# TC_board.net
KiCad netlist of a schematic drawn in EAGLE
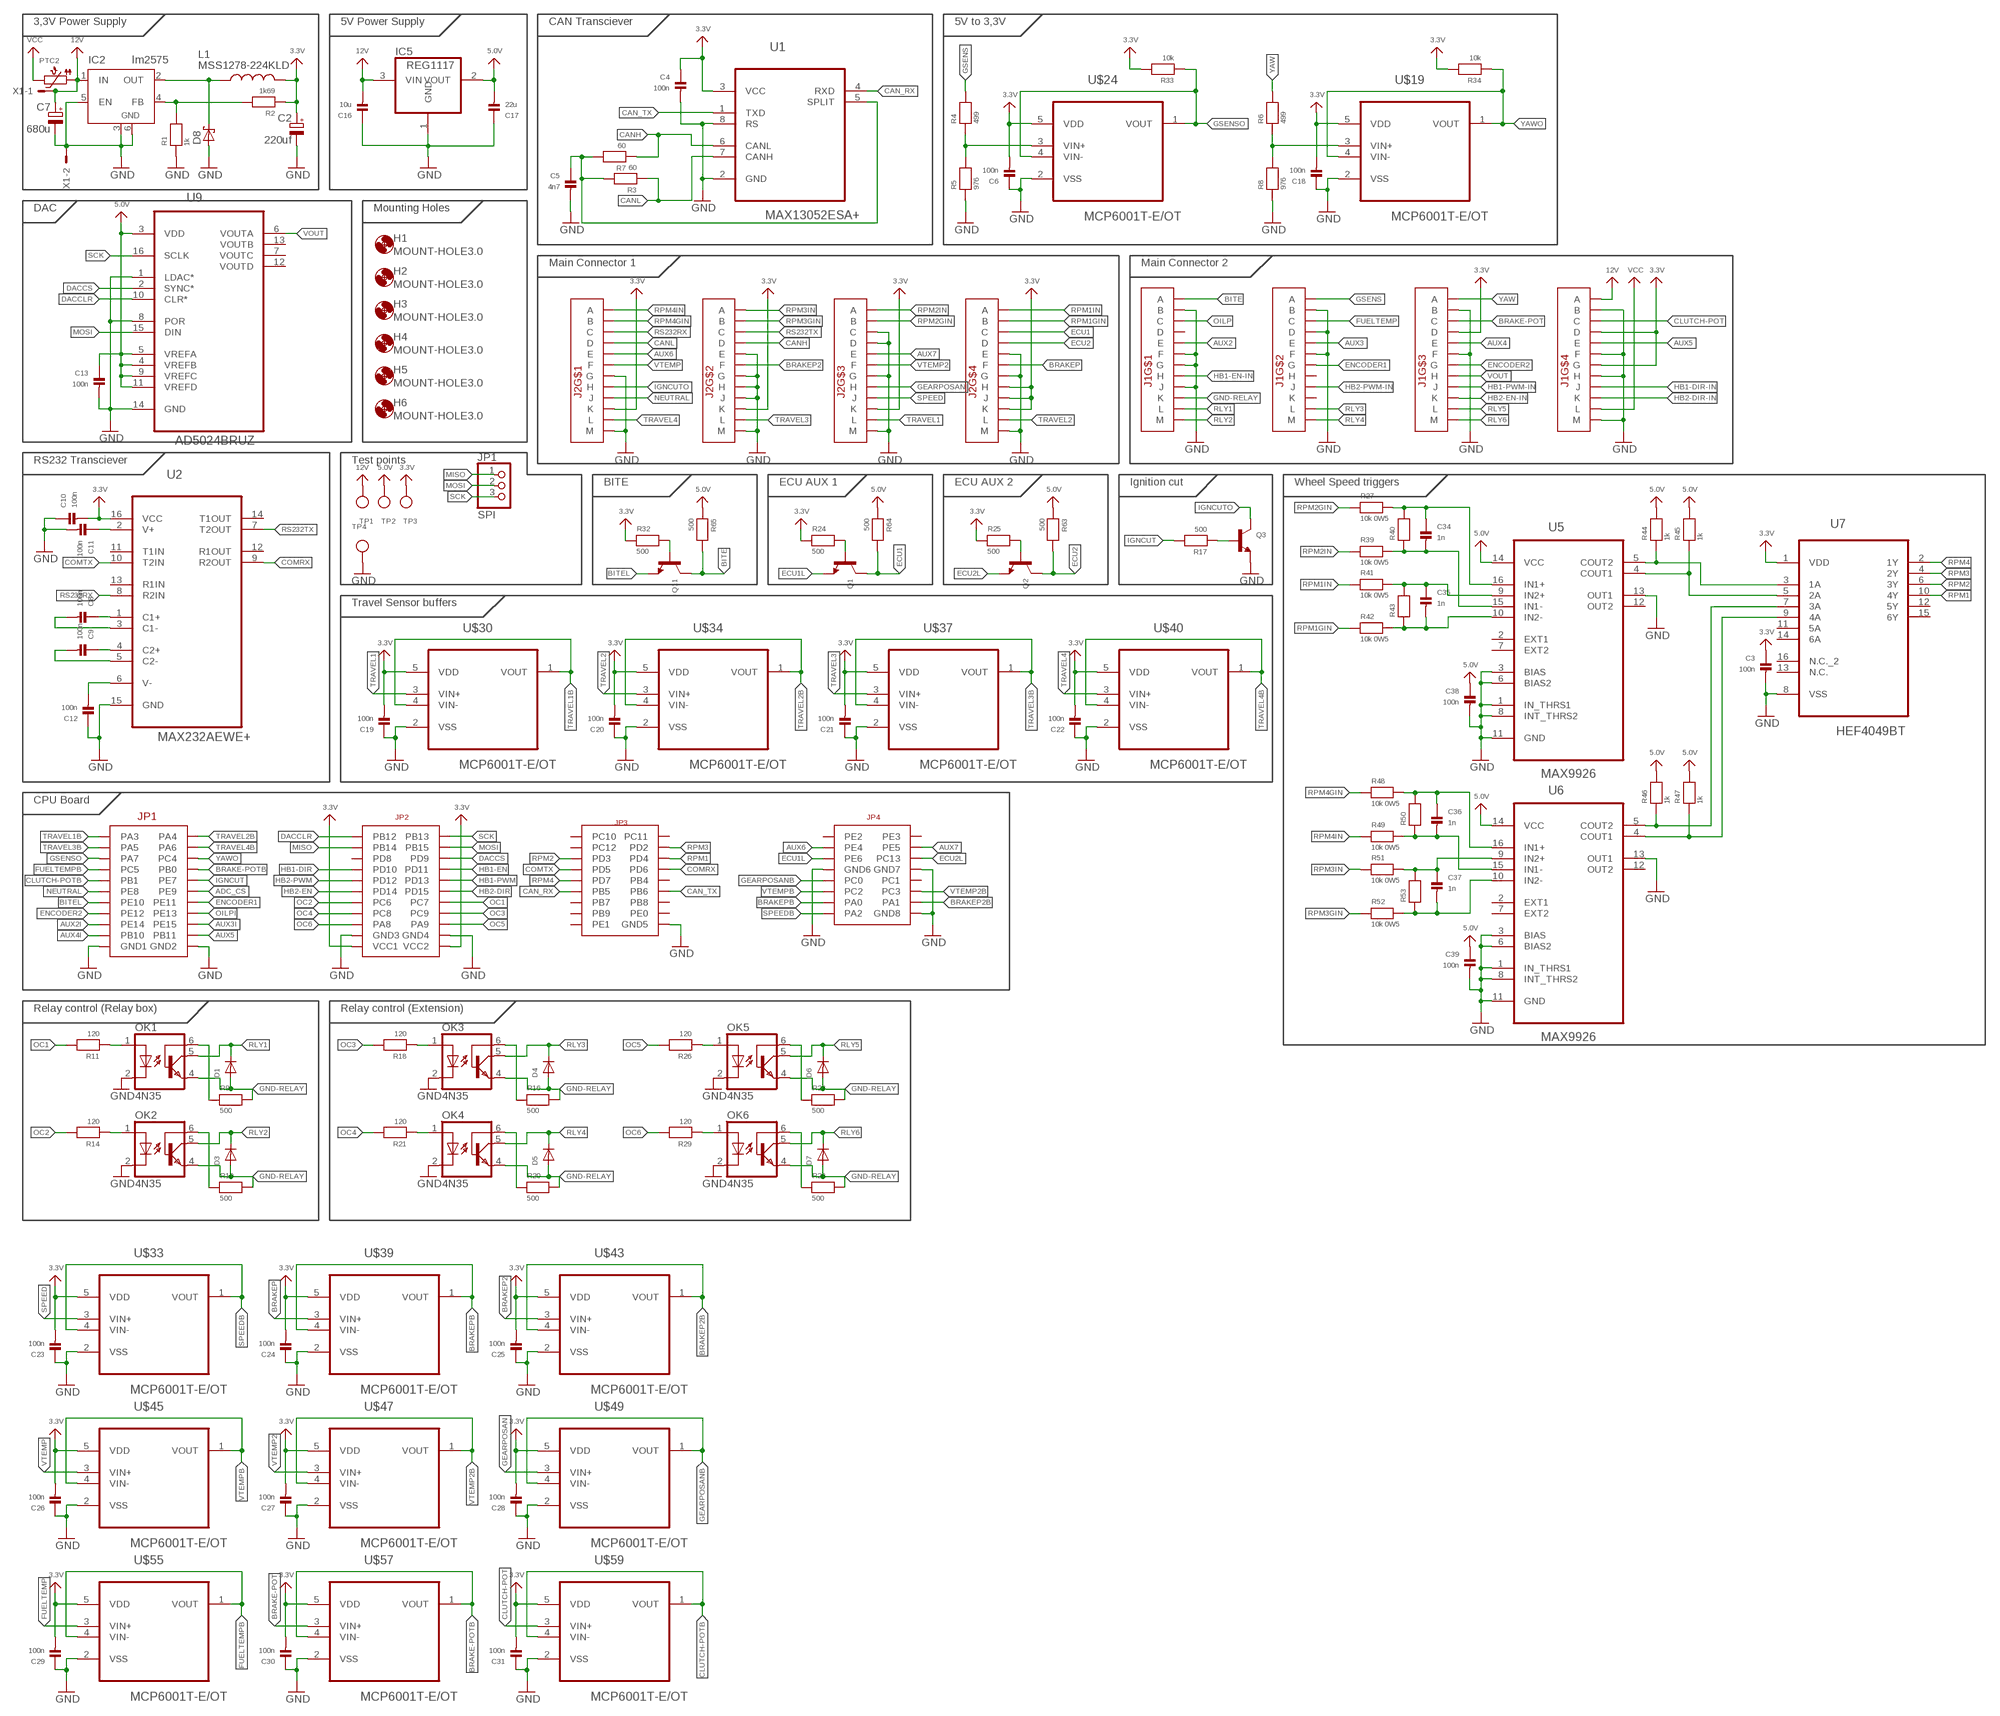
[diagram p0: schematic, sheet 1, part 1 of 2]
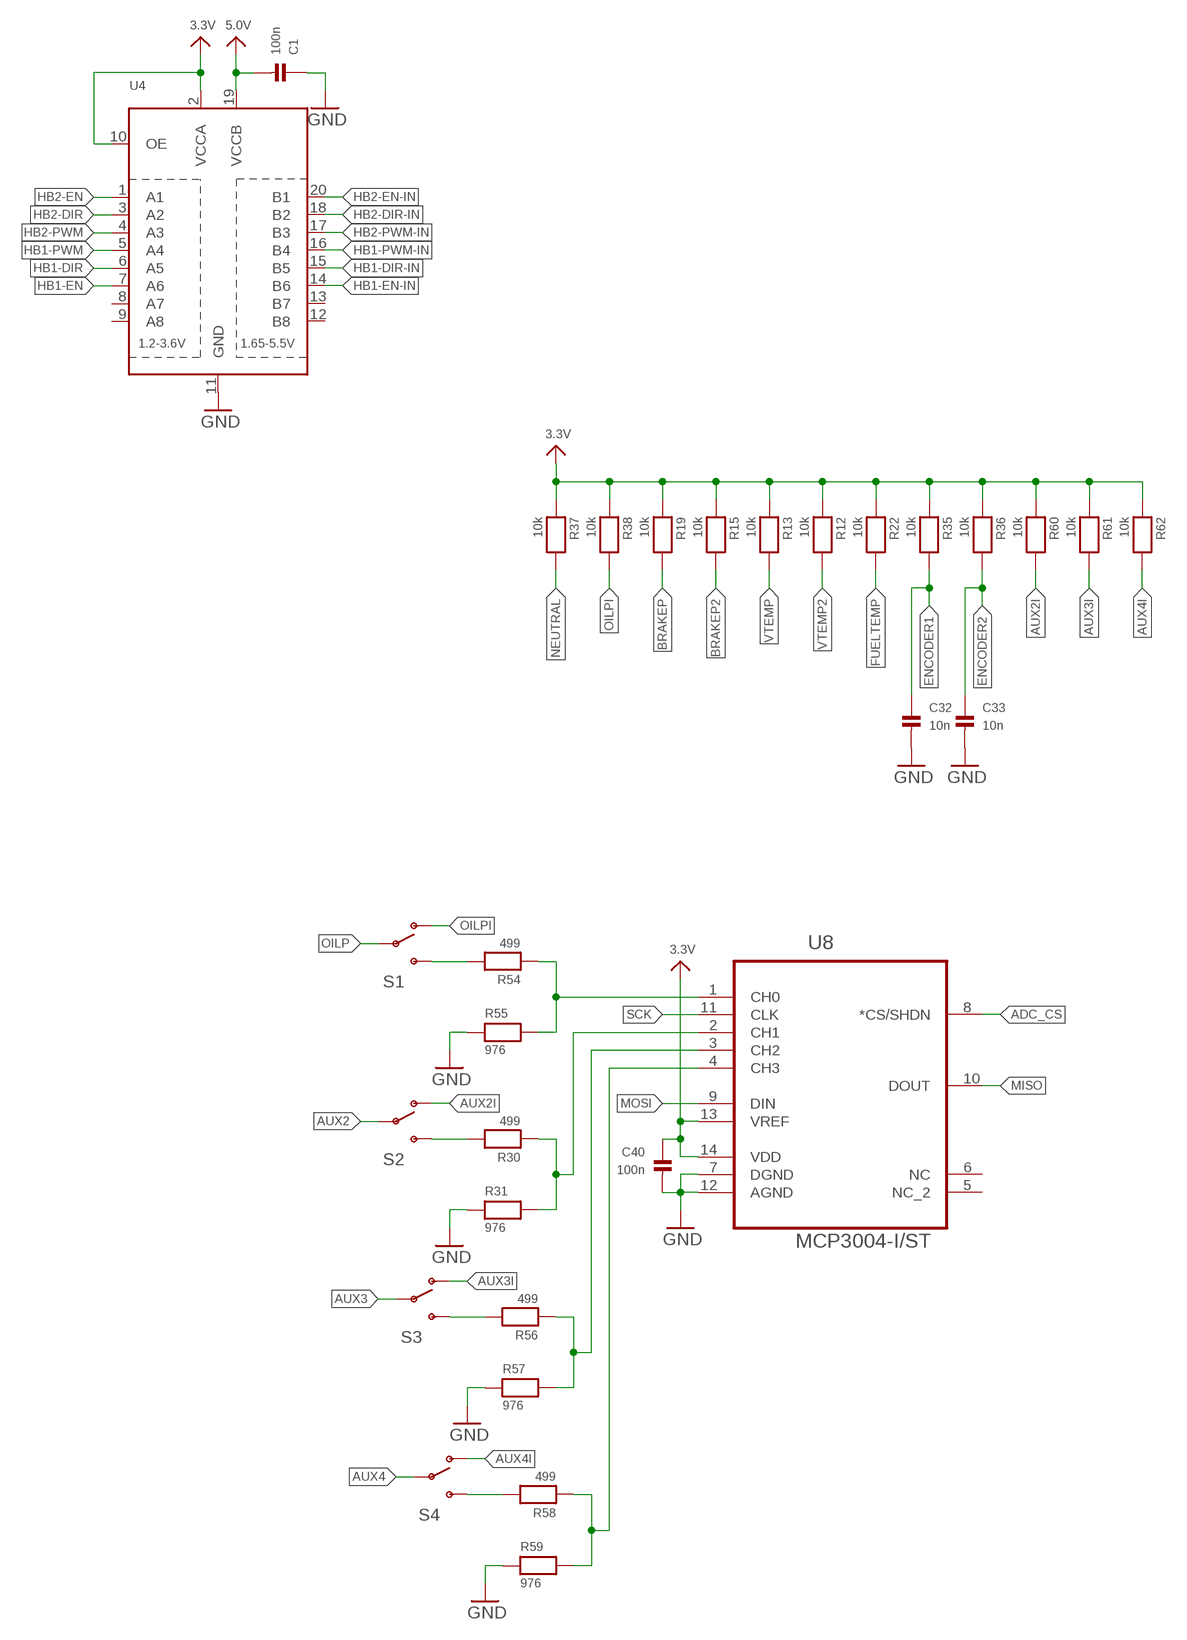
[diagram p1: schematic, sheet 1, part 2 of 2]

(export (version "E")
  (design (tool "Eeschema 10.0.6"))
  (components
    (comp (ref "C1")
      (value "100n")
      (footprint "eagle-import:_0603")
      (libsource (lib "eagle-import") (part "CAP_CERAMIC_0603"))
    )
    (comp (ref "C2")
      (value "220uf")
      (footprint "eagle-import:E3,5-8")
      (libsource (lib "eagle-import") (part "CPOL-EUE3.5-8"))
    )
    (comp (ref "C3")
      (value "100n")
      (footprint "eagle-import:_0603")
      (libsource (lib "eagle-import") (part "CAP_CERAMIC_0603"))
    )
    (comp (ref "C4")
      (value "100n")
      (footprint "eagle-import:_0603")
      (libsource (lib "eagle-import") (part "CAP_CERAMIC_0603"))
    )
    (comp (ref "C5")
      (value "4n7")
      (footprint "eagle-import:_0603")
      (libsource (lib "eagle-import") (part "CAP_CERAMIC_0603"))
    )
    (comp (ref "C6")
      (value "100n")
      (footprint "eagle-import:_0603")
      (libsource (lib "eagle-import") (part "CAP_CERAMIC_0603"))
    )
    (comp (ref "C7")
      (value "680u")
      (footprint "eagle-import:E5-10,5")
      (libsource (lib "eagle-import") (part "CPOL-EUE5-10.5"))
    )
    (comp (ref "C8")
      (value "100n")
      (footprint "eagle-import:_0603")
      (libsource (lib "eagle-import") (part "CAP_CERAMIC_0603"))
    )
    (comp (ref "C9")
      (value "100n")
      (footprint "eagle-import:_0603")
      (libsource (lib "eagle-import") (part "CAP_CERAMIC_0603"))
    )
    (comp (ref "C10")
      (value "100n")
      (footprint "eagle-import:_0603")
      (libsource (lib "eagle-import") (part "CAP_CERAMIC_0603"))
    )
    (comp (ref "C11")
      (value "100n")
      (footprint "eagle-import:_0603")
      (libsource (lib "eagle-import") (part "CAP_CERAMIC_0603"))
    )
    (comp (ref "C12")
      (value "100n")
      (footprint "eagle-import:_0603")
      (libsource (lib "eagle-import") (part "CAP_CERAMIC_0603"))
    )
    (comp (ref "C13")
      (value "100n")
      (footprint "eagle-import:_0603")
      (libsource (lib "eagle-import") (part "CAP_CERAMIC_0603"))
    )
    (comp (ref "C16")
      (value "10u")
      (footprint "eagle-import:_0805")
      (libsource (lib "eagle-import") (part "CAP_CERAMIC_0805"))
    )
    (comp (ref "C17")
      (value "22u")
      (footprint "eagle-import:_0805")
      (libsource (lib "eagle-import") (part "CAP_CERAMIC_0805"))
    )
    (comp (ref "C18")
      (value "100n")
      (footprint "eagle-import:_0603")
      (libsource (lib "eagle-import") (part "CAP_CERAMIC_0603"))
    )
    (comp (ref "C19")
      (value "100n")
      (footprint "eagle-import:_0603")
      (libsource (lib "eagle-import") (part "CAP_CERAMIC_0603"))
    )
    (comp (ref "C20")
      (value "100n")
      (footprint "eagle-import:_0603")
      (libsource (lib "eagle-import") (part "CAP_CERAMIC_0603"))
    )
    (comp (ref "C21")
      (value "100n")
      (footprint "eagle-import:_0603")
      (libsource (lib "eagle-import") (part "CAP_CERAMIC_0603"))
    )
    (comp (ref "C22")
      (value "100n")
      (footprint "eagle-import:_0603")
      (libsource (lib "eagle-import") (part "CAP_CERAMIC_0603"))
    )
    (comp (ref "C23")
      (value "100n")
      (footprint "eagle-import:_0603")
      (libsource (lib "eagle-import") (part "CAP_CERAMIC_0603"))
    )
    (comp (ref "C24")
      (value "100n")
      (footprint "eagle-import:_0603")
      (libsource (lib "eagle-import") (part "CAP_CERAMIC_0603"))
    )
    (comp (ref "C25")
      (value "100n")
      (footprint "eagle-import:_0603")
      (libsource (lib "eagle-import") (part "CAP_CERAMIC_0603"))
    )
    (comp (ref "C26")
      (value "100n")
      (footprint "eagle-import:_0603")
      (libsource (lib "eagle-import") (part "CAP_CERAMIC_0603"))
    )
    (comp (ref "C27")
      (value "100n")
      (footprint "eagle-import:_0603")
      (libsource (lib "eagle-import") (part "CAP_CERAMIC_0603"))
    )
    (comp (ref "C28")
      (value "100n")
      (footprint "eagle-import:_0603")
      (libsource (lib "eagle-import") (part "CAP_CERAMIC_0603"))
    )
    (comp (ref "C29")
      (value "100n")
      (footprint "eagle-import:_0603")
      (libsource (lib "eagle-import") (part "CAP_CERAMIC_0603"))
    )
    (comp (ref "C30")
      (value "100n")
      (footprint "eagle-import:_0603")
      (libsource (lib "eagle-import") (part "CAP_CERAMIC_0603"))
    )
    (comp (ref "C31")
      (value "100n")
      (footprint "eagle-import:_0603")
      (libsource (lib "eagle-import") (part "CAP_CERAMIC_0603"))
    )
    (comp (ref "C32")
      (value "10n")
      (footprint "eagle-import:_0603")
      (libsource (lib "eagle-import") (part "CAP_CERAMIC_0603"))
    )
    (comp (ref "C33")
      (value "10n")
      (footprint "eagle-import:_0603")
      (libsource (lib "eagle-import") (part "CAP_CERAMIC_0603"))
    )
    (comp (ref "C34")
      (value "1n")
      (footprint "eagle-import:_0603")
      (libsource (lib "eagle-import") (part "CAP_CERAMIC_0603"))
    )
    (comp (ref "C35")
      (value "1n")
      (footprint "eagle-import:_0603")
      (libsource (lib "eagle-import") (part "CAP_CERAMIC_0603"))
    )
    (comp (ref "C36")
      (value "1n")
      (footprint "eagle-import:_0603")
      (libsource (lib "eagle-import") (part "CAP_CERAMIC_0603"))
    )
    (comp (ref "C37")
      (value "1n")
      (footprint "eagle-import:_0603")
      (libsource (lib "eagle-import") (part "CAP_CERAMIC_0603"))
    )
    (comp (ref "C38")
      (value "100n")
      (footprint "eagle-import:_0603")
      (libsource (lib "eagle-import") (part "CAP_CERAMIC_0603"))
    )
    (comp (ref "C39")
      (value "100n")
      (footprint "eagle-import:_0603")
      (libsource (lib "eagle-import") (part "CAP_CERAMIC_0603"))
    )
    (comp (ref "C40")
      (value "100n")
      (footprint "eagle-import:_0603")
      (libsource (lib "eagle-import") (part "CAP_CERAMIC_0603"))
    )
    (comp (ref "D1")
      (value "DIODESOD-323F")
      (footprint "eagle-import:SOD-323F")
      (libsource (lib "eagle-import") (part "DIODESOD-323F"))
    )
    (comp (ref "D3")
      (value "DIODESOD-323F")
      (footprint "eagle-import:SOD-323F")
      (libsource (lib "eagle-import") (part "DIODESOD-323F"))
    )
    (comp (ref "D4")
      (value "DIODESOD-323F")
      (footprint "eagle-import:SOD-323F")
      (libsource (lib "eagle-import") (part "DIODESOD-323F"))
    )
    (comp (ref "D5")
      (value "DIODESOD-323F")
      (footprint "eagle-import:SOD-323F")
      (libsource (lib "eagle-import") (part "DIODESOD-323F"))
    )
    (comp (ref "D6")
      (value "DIODESOD-323F")
      (footprint "eagle-import:SOD-323F")
      (libsource (lib "eagle-import") (part "DIODESOD-323F"))
    )
    (comp (ref "D7")
      (value "DIODESOD-323F")
      (footprint "eagle-import:SOD-323F")
      (libsource (lib "eagle-import") (part "DIODESOD-323F"))
    )
    (comp (ref "D8")
      (value "SCHOTTKY-DIODESMC")
      (footprint "eagle-import:SMC")
      (libsource (lib "eagle-import") (part "SCHOTTKY-DIODESMC"))
    )
    (comp (ref "H1")
      (value "MOUNT-HOLE3.0")
      (footprint "eagle-import:3,0")
      (libsource (lib "eagle-import") (part "MOUNT-HOLE3.0"))
    )
    (comp (ref "H2")
      (value "MOUNT-HOLE3.0")
      (footprint "eagle-import:3,0")
      (libsource (lib "eagle-import") (part "MOUNT-HOLE3.0"))
    )
    (comp (ref "H3")
      (value "MOUNT-HOLE3.0")
      (footprint "eagle-import:3,0")
      (libsource (lib "eagle-import") (part "MOUNT-HOLE3.0"))
    )
    (comp (ref "H4")
      (value "MOUNT-HOLE3.0")
      (footprint "eagle-import:3,0")
      (libsource (lib "eagle-import") (part "MOUNT-HOLE3.0"))
    )
    (comp (ref "H5")
      (value "MOUNT-HOLE3.0")
      (footprint "eagle-import:3,0")
      (libsource (lib "eagle-import") (part "MOUNT-HOLE3.0"))
    )
    (comp (ref "H6")
      (value "MOUNT-HOLE3.0")
      (footprint "eagle-import:3,0")
      (libsource (lib "eagle-import") (part "MOUNT-HOLE3.0"))
    )
    (comp (ref "IC2")
      (value "lm2575")
      (footprint "eagle-import:TO263-5")
      (libsource (lib "eagle-import") (part "LM2596S"))
    )
    (comp (ref "IC5")
      (value "REG1117")
      (footprint "eagle-import:SOT223")
      (libsource (lib "eagle-import") (part "REG1117"))
    )
    (comp (ref "J1")
      (value "CON1")
      (footprint "eagle-import:AUTOCONNECTOR")
      (libsource (lib "eagle-import") (part "AUTOCONNECTOR"))
    )
    (comp (ref "J2")
      (value "CON1")
      (footprint "eagle-import:AUTOCONNECTOR")
      (libsource (lib "eagle-import") (part "AUTOCONNECTOR"))
    )
    (comp (ref "JP1")
      (value "SPI")
      (footprint "eagle-import:1X03")
      (libsource (lib "eagle-import") (part "PINHD-1X3"))
    )
    (comp (ref "L1")
      (value "MSS1278-224KLD")
      (footprint "eagle-import:CDRH125")
      (libsource (lib "eagle-import") (part "INDUCTORPWR"))
    )
    (comp (ref "OK1")
      (value "4N35")
      (footprint "eagle-import:DIL06")
      (fields (field (name "MF") "FAIRCHILD SEMICONDUCTOR"))
      (libsource (lib "eagle-import") (part "4N35"))
    )
    (comp (ref "OK2")
      (value "4N35")
      (footprint "eagle-import:DIL06")
      (fields (field (name "MF") "FAIRCHILD SEMICONDUCTOR"))
      (libsource (lib "eagle-import") (part "4N35"))
    )
    (comp (ref "OK3")
      (value "4N35")
      (footprint "eagle-import:DIL06")
      (fields (field (name "MF") "FAIRCHILD SEMICONDUCTOR"))
      (libsource (lib "eagle-import") (part "4N35"))
    )
    (comp (ref "OK4")
      (value "4N35")
      (footprint "eagle-import:DIL06")
      (fields (field (name "MF") "FAIRCHILD SEMICONDUCTOR"))
      (libsource (lib "eagle-import") (part "4N35"))
    )
    (comp (ref "OK5")
      (value "4N35")
      (footprint "eagle-import:DIL06")
      (fields (field (name "MF") "FAIRCHILD SEMICONDUCTOR"))
      (libsource (lib "eagle-import") (part "4N35"))
    )
    (comp (ref "OK6")
      (value "4N35")
      (footprint "eagle-import:DIL06")
      (fields (field (name "MF") "FAIRCHILD SEMICONDUCTOR"))
      (libsource (lib "eagle-import") (part "4N35"))
    )
    (comp (ref "PTC2")
      (value "PTC1812")
      (footprint "eagle-import:PTC1812")
      (libsource (lib "eagle-import") (part "PTC1812"))
    )
    (comp (ref "Q1")
      (value "TRANSISTOR_NPNWIDE")
      (footprint "eagle-import:SOT23-WIDE")
      (libsource (lib "eagle-import") (part "TRANSISTOR_NPNWIDE"))
    )
    (comp (ref "Q2")
      (value "TRANSISTOR_NPNWIDE")
      (footprint "eagle-import:SOT23-WIDE")
      (libsource (lib "eagle-import") (part "TRANSISTOR_NPNWIDE"))
    )
    (comp (ref "Q3")
      (value "TRANSISTOR_NPNWIDE")
      (footprint "eagle-import:SOT23-WIDE")
      (libsource (lib "eagle-import") (part "TRANSISTOR_NPNWIDE"))
    )
    (comp (ref "Q11")
      (value "TRANSISTOR_NPNWIDE")
      (footprint "eagle-import:SOT23-WIDE")
      (libsource (lib "eagle-import") (part "TRANSISTOR_NPNWIDE"))
    )
    (comp (ref "R1")
      (value "1k")
      (footprint "eagle-import:_0603")
      (libsource (lib "eagle-import") (part "RESISTOR_0603"))
    )
    (comp (ref "R2")
      (value "1k69")
      (footprint "eagle-import:_0603")
      (libsource (lib "eagle-import") (part "RESISTOR_0603"))
    )
    (comp (ref "R3")
      (value "60")
      (footprint "eagle-import:_0603")
      (libsource (lib "eagle-import") (part "RESISTOR_0603"))
    )
    (comp (ref "R4")
      (value "499")
      (footprint "eagle-import:_0603")
      (libsource (lib "eagle-import") (part "RESISTOR_0603"))
    )
    (comp (ref "R5")
      (value "976")
      (footprint "eagle-import:_0603")
      (libsource (lib "eagle-import") (part "RESISTOR_0603"))
    )
    (comp (ref "R6")
      (value "499")
      (footprint "eagle-import:_0603")
      (libsource (lib "eagle-import") (part "RESISTOR_0603"))
    )
    (comp (ref "R7")
      (value "60")
      (footprint "eagle-import:_0603")
      (libsource (lib "eagle-import") (part "RESISTOR_0603"))
    )
    (comp (ref "R8")
      (value "976")
      (footprint "eagle-import:_0603")
      (libsource (lib "eagle-import") (part "RESISTOR_0603"))
    )
    (comp (ref "R9")
      (value "500")
      (footprint "eagle-import:_0603")
      (libsource (lib "eagle-import") (part "RESISTOR_0603"))
    )
    (comp (ref "R10")
      (value "500")
      (footprint "eagle-import:_0603")
      (libsource (lib "eagle-import") (part "RESISTOR_0603"))
    )
    (comp (ref "R11")
      (value "120")
      (footprint "eagle-import:_0603")
      (libsource (lib "eagle-import") (part "RESISTOR_0603"))
    )
    (comp (ref "R12")
      (value "10k")
      (footprint "eagle-import:_0603")
      (libsource (lib "eagle-import") (part "RESISTOR_0603"))
    )
    (comp (ref "R13")
      (value "10k")
      (footprint "eagle-import:_0603")
      (libsource (lib "eagle-import") (part "RESISTOR_0603"))
    )
    (comp (ref "R14")
      (value "120")
      (footprint "eagle-import:_0603")
      (libsource (lib "eagle-import") (part "RESISTOR_0603"))
    )
    (comp (ref "R15")
      (value "10k")
      (footprint "eagle-import:_0603")
      (libsource (lib "eagle-import") (part "RESISTOR_0603"))
    )
    (comp (ref "R16")
      (value "500")
      (footprint "eagle-import:_0603")
      (libsource (lib "eagle-import") (part "RESISTOR_0603"))
    )
    (comp (ref "R17")
      (value "500")
      (footprint "eagle-import:_0603")
      (libsource (lib "eagle-import") (part "RESISTOR_0603"))
    )
    (comp (ref "R18")
      (value "120")
      (footprint "eagle-import:_0603")
      (libsource (lib "eagle-import") (part "RESISTOR_0603"))
    )
    (comp (ref "R19")
      (value "10k")
      (footprint "eagle-import:_0603")
      (libsource (lib "eagle-import") (part "RESISTOR_0603"))
    )
    (comp (ref "R20")
      (value "500")
      (footprint "eagle-import:_0603")
      (libsource (lib "eagle-import") (part "RESISTOR_0603"))
    )
    (comp (ref "R21")
      (value "120")
      (footprint "eagle-import:_0603")
      (libsource (lib "eagle-import") (part "RESISTOR_0603"))
    )
    (comp (ref "R22")
      (value "10k")
      (footprint "eagle-import:_0603")
      (libsource (lib "eagle-import") (part "RESISTOR_0603"))
    )
    (comp (ref "R23")
      (value "500")
      (footprint "eagle-import:_0603")
      (libsource (lib "eagle-import") (part "RESISTOR_0603"))
    )
    (comp (ref "R24")
      (value "500")
      (footprint "eagle-import:_0603")
      (libsource (lib "eagle-import") (part "RESISTOR_0603"))
    )
    (comp (ref "R25")
      (value "500")
      (footprint "eagle-import:_0603")
      (libsource (lib "eagle-import") (part "RESISTOR_0603"))
    )
    (comp (ref "R26")
      (value "120")
      (footprint "eagle-import:_0603")
      (libsource (lib "eagle-import") (part "RESISTOR_0603"))
    )
    (comp (ref "R27")
      (value "10k 0W5")
      (footprint "eagle-import:_0805")
      (libsource (lib "eagle-import") (part "RESISTOR_0805"))
    )
    (comp (ref "R28")
      (value "500")
      (footprint "eagle-import:_0603")
      (libsource (lib "eagle-import") (part "RESISTOR_0603"))
    )
    (comp (ref "R29")
      (value "120")
      (footprint "eagle-import:_0603")
      (libsource (lib "eagle-import") (part "RESISTOR_0603"))
    )
    (comp (ref "R30")
      (value "499")
      (footprint "eagle-import:_0603")
      (libsource (lib "eagle-import") (part "RESISTOR_0603"))
    )
    (comp (ref "R31")
      (value "976")
      (footprint "eagle-import:_0603")
      (libsource (lib "eagle-import") (part "RESISTOR_0603"))
    )
    (comp (ref "R32")
      (value "500")
      (footprint "eagle-import:_0603")
      (libsource (lib "eagle-import") (part "RESISTOR_0603"))
    )
    (comp (ref "R33")
      (value "10k")
      (footprint "eagle-import:_0603")
      (libsource (lib "eagle-import") (part "RESISTOR_0603"))
    )
    (comp (ref "R34")
      (value "10k")
      (footprint "eagle-import:_0603")
      (libsource (lib "eagle-import") (part "RESISTOR_0603"))
    )
    (comp (ref "R35")
      (value "10k")
      (footprint "eagle-import:_0603")
      (libsource (lib "eagle-import") (part "RESISTOR_0603"))
    )
    (comp (ref "R36")
      (value "10k")
      (footprint "eagle-import:_0603")
      (libsource (lib "eagle-import") (part "RESISTOR_0603"))
    )
    (comp (ref "R37")
      (value "10k")
      (footprint "eagle-import:_0603")
      (libsource (lib "eagle-import") (part "RESISTOR_0603"))
    )
    (comp (ref "R38")
      (value "10k")
      (footprint "eagle-import:_0603")
      (libsource (lib "eagle-import") (part "RESISTOR_0603"))
    )
    (comp (ref "R39")
      (value "10k 0W5")
      (footprint "eagle-import:_0805")
      (libsource (lib "eagle-import") (part "RESISTOR_0805"))
    )
    (comp (ref "R40")
      (value "RESISTOR_0805")
      (footprint "eagle-import:_0805")
      (libsource (lib "eagle-import") (part "RESISTOR_0805"))
    )
    (comp (ref "R41")
      (value "10k 0W5")
      (footprint "eagle-import:_0805")
      (libsource (lib "eagle-import") (part "RESISTOR_0805"))
    )
    (comp (ref "R42")
      (value "10k 0W5")
      (footprint "eagle-import:_0805")
      (libsource (lib "eagle-import") (part "RESISTOR_0805"))
    )
    (comp (ref "R43")
      (value "RESISTOR_0805")
      (footprint "eagle-import:_0805")
      (libsource (lib "eagle-import") (part "RESISTOR_0805"))
    )
    (comp (ref "R44")
      (value "1k")
      (footprint "eagle-import:_0603")
      (libsource (lib "eagle-import") (part "RESISTOR_0603"))
    )
    (comp (ref "R45")
      (value "1k")
      (footprint "eagle-import:_0603")
      (libsource (lib "eagle-import") (part "RESISTOR_0603"))
    )
    (comp (ref "R46")
      (value "1k")
      (footprint "eagle-import:_0603")
      (libsource (lib "eagle-import") (part "RESISTOR_0603"))
    )
    (comp (ref "R47")
      (value "1k")
      (footprint "eagle-import:_0603")
      (libsource (lib "eagle-import") (part "RESISTOR_0603"))
    )
    (comp (ref "R48")
      (value "10k 0W5")
      (footprint "eagle-import:_0805")
      (libsource (lib "eagle-import") (part "RESISTOR_0805"))
    )
    (comp (ref "R49")
      (value "10k 0W5")
      (footprint "eagle-import:_0805")
      (libsource (lib "eagle-import") (part "RESISTOR_0805"))
    )
    (comp (ref "R50")
      (value "RESISTOR_0805")
      (footprint "eagle-import:_0805")
      (libsource (lib "eagle-import") (part "RESISTOR_0805"))
    )
    (comp (ref "R51")
      (value "10k 0W5")
      (footprint "eagle-import:_0805")
      (libsource (lib "eagle-import") (part "RESISTOR_0805"))
    )
    (comp (ref "R52")
      (value "10k 0W5")
      (footprint "eagle-import:_0805")
      (libsource (lib "eagle-import") (part "RESISTOR_0805"))
    )
    (comp (ref "R53")
      (value "RESISTOR_0805")
      (footprint "eagle-import:_0805")
      (libsource (lib "eagle-import") (part "RESISTOR_0805"))
    )
    (comp (ref "R54")
      (value "499")
      (footprint "eagle-import:_0603")
      (libsource (lib "eagle-import") (part "RESISTOR_0603"))
    )
    (comp (ref "R55")
      (value "976")
      (footprint "eagle-import:_0603")
      (libsource (lib "eagle-import") (part "RESISTOR_0603"))
    )
    (comp (ref "R56")
      (value "499")
      (footprint "eagle-import:_0603")
      (libsource (lib "eagle-import") (part "RESISTOR_0603"))
    )
    (comp (ref "R57")
      (value "976")
      (footprint "eagle-import:_0603")
      (libsource (lib "eagle-import") (part "RESISTOR_0603"))
    )
    (comp (ref "R58")
      (value "499")
      (footprint "eagle-import:_0603")
      (libsource (lib "eagle-import") (part "RESISTOR_0603"))
    )
    (comp (ref "R59")
      (value "976")
      (footprint "eagle-import:_0603")
      (libsource (lib "eagle-import") (part "RESISTOR_0603"))
    )
    (comp (ref "R60")
      (value "10k")
      (footprint "eagle-import:_0603")
      (libsource (lib "eagle-import") (part "RESISTOR_0603"))
    )
    (comp (ref "R61")
      (value "10k")
      (footprint "eagle-import:_0603")
      (libsource (lib "eagle-import") (part "RESISTOR_0603"))
    )
    (comp (ref "R62")
      (value "10k")
      (footprint "eagle-import:_0603")
      (libsource (lib "eagle-import") (part "RESISTOR_0603"))
    )
    (comp (ref "R63")
      (value "500")
      (footprint "eagle-import:_0603")
      (libsource (lib "eagle-import") (part "RESISTOR_0603"))
    )
    (comp (ref "R64")
      (value "500")
      (footprint "eagle-import:_0603")
      (libsource (lib "eagle-import") (part "RESISTOR_0603"))
    )
    (comp (ref "R65")
      (value "500")
      (footprint "eagle-import:_0603")
      (libsource (lib "eagle-import") (part "RESISTOR_0603"))
    )
    (comp (ref "S1")
      (value "SWITCH-SPDT-SMD-A")
      (footprint "eagle-import:SWITCH-SPST-SMD-A")
      (libsource (lib "eagle-import") (part "SWITCH-SPDT-SMD-A"))
    )
    (comp (ref "S2")
      (value "SWITCH-SPDT-SMD-A")
      (footprint "eagle-import:SWITCH-SPST-SMD-A")
      (libsource (lib "eagle-import") (part "SWITCH-SPDT-SMD-A"))
    )
    (comp (ref "S3")
      (value "SWITCH-SPDT-SMD-A")
      (footprint "eagle-import:SWITCH-SPST-SMD-A")
      (libsource (lib "eagle-import") (part "SWITCH-SPDT-SMD-A"))
    )
    (comp (ref "S4")
      (value "SWITCH-SPDT-SMD-A")
      (footprint "eagle-import:SWITCH-SPST-SMD-A")
      (libsource (lib "eagle-import") (part "SWITCH-SPDT-SMD-A"))
    )
    (comp (ref "TP1")
      (value "TESTPOINT")
      (footprint "eagle-import:TESTPOINT_SMT")
      (libsource (lib "eagle-import") (part "TESTPOINT"))
    )
    (comp (ref "TP2")
      (value "TESTPOINT")
      (footprint "eagle-import:TESTPOINT_SMT")
      (libsource (lib "eagle-import") (part "TESTPOINT"))
    )
    (comp (ref "TP3")
      (value "TESTPOINT")
      (footprint "eagle-import:TESTPOINT_SMT")
      (libsource (lib "eagle-import") (part "TESTPOINT"))
    )
    (comp (ref "TP4")
      (value "TESTPOINT")
      (footprint "eagle-import:TESTPOINT_SMT")
      (libsource (lib "eagle-import") (part "TESTPOINT"))
    )
    (comp (ref "U$1")
      (value "CPU-BOARD")
      (footprint "eagle-import:CPU-BOARD-JP1")
      (libsource (lib "eagle-import") (part "CPU-BOARD"))
    )
    (comp (ref "U$19")
      (value "MCP6001T-E/OT")
      (footprint "eagle-import:SOT95P270X145-5N")
      (libsource (lib "eagle-import") (part "MCP6001T-E/OT"))
    )
    (comp (ref "U$24")
      (value "MCP6001T-E/OT")
      (footprint "eagle-import:SOT95P270X145-5N")
      (libsource (lib "eagle-import") (part "MCP6001T-E/OT"))
    )
    (comp (ref "U$30")
      (value "MCP6001T-E/OT")
      (footprint "eagle-import:SOT95P270X145-5N")
      (libsource (lib "eagle-import") (part "MCP6001T-E/OT"))
    )
    (comp (ref "U$33")
      (value "MCP6001T-E/OT")
      (footprint "eagle-import:SOT95P270X145-5N")
      (libsource (lib "eagle-import") (part "MCP6001T-E/OT"))
    )
    (comp (ref "U$34")
      (value "MCP6001T-E/OT")
      (footprint "eagle-import:SOT95P270X145-5N")
      (libsource (lib "eagle-import") (part "MCP6001T-E/OT"))
    )
    (comp (ref "U$37")
      (value "MCP6001T-E/OT")
      (footprint "eagle-import:SOT95P270X145-5N")
      (libsource (lib "eagle-import") (part "MCP6001T-E/OT"))
    )
    (comp (ref "U$39")
      (value "MCP6001T-E/OT")
      (footprint "eagle-import:SOT95P270X145-5N")
      (libsource (lib "eagle-import") (part "MCP6001T-E/OT"))
    )
    (comp (ref "U$40")
      (value "MCP6001T-E/OT")
      (footprint "eagle-import:SOT95P270X145-5N")
      (libsource (lib "eagle-import") (part "MCP6001T-E/OT"))
    )
    (comp (ref "U$43")
      (value "MCP6001T-E/OT")
      (footprint "eagle-import:SOT95P270X145-5N")
      (libsource (lib "eagle-import") (part "MCP6001T-E/OT"))
    )
    (comp (ref "U$45")
      (value "MCP6001T-E/OT")
      (footprint "eagle-import:SOT95P270X145-5N")
      (libsource (lib "eagle-import") (part "MCP6001T-E/OT"))
    )
    (comp (ref "U$47")
      (value "MCP6001T-E/OT")
      (footprint "eagle-import:SOT95P270X145-5N")
      (libsource (lib "eagle-import") (part "MCP6001T-E/OT"))
    )
    (comp (ref "U$49")
      (value "MCP6001T-E/OT")
      (footprint "eagle-import:SOT95P270X145-5N")
      (libsource (lib "eagle-import") (part "MCP6001T-E/OT"))
    )
    (comp (ref "U$55")
      (value "MCP6001T-E/OT")
      (footprint "eagle-import:SOT95P270X145-5N")
      (libsource (lib "eagle-import") (part "MCP6001T-E/OT"))
    )
    (comp (ref "U$57")
      (value "MCP6001T-E/OT")
      (footprint "eagle-import:SOT95P270X145-5N")
      (libsource (lib "eagle-import") (part "MCP6001T-E/OT"))
    )
    (comp (ref "U$59")
      (value "MCP6001T-E/OT")
      (footprint "eagle-import:SOT95P270X145-5N")
      (libsource (lib "eagle-import") (part "MCP6001T-E/OT"))
    )
    (comp (ref "U1")
      (value "MAX13052ESA+")
      (footprint "eagle-import:SOIC127P600X175-8N")
      (libsource (lib "eagle-import") (part "MAX13052ESA+"))
    )
    (comp (ref "U2")
      (value "MAX232AEWE+")
      (footprint "eagle-import:SOIC127P1032X265-16N")
      (libsource (lib "eagle-import") (part "MAX232AEWE+"))
    )
    (comp (ref "U4")
      (value "TXB0108PWR")
      (footprint "eagle-import:TSSOP20")
      (libsource (lib "eagle-import") (part "TXB0108PWR"))
    )
    (comp (ref "U5")
      (value "MAX9926")
      (footprint "eagle-import:SOP63P600X175-16N")
      (fields (field (name "MPN") "MAX9927AEE+"))
      (libsource (lib "eagle-import") (part "MAX9927AEE+"))
    )
    (comp (ref "U6")
      (value "MAX9926")
      (footprint "eagle-import:SOP63P600X175-16N")
      (fields (field (name "MPN") "MAX9927AEE+"))
      (libsource (lib "eagle-import") (part "MAX9927AEE+"))
    )
    (comp (ref "U7")
      (value "HEF4049BT")
      (footprint "eagle-import:SOIC127P600X175-16N")
      (libsource (lib "eagle-import") (part "HEF4049BT"))
    )
    (comp (ref "U8")
      (value "MCP3004-I/ST")
      (footprint "eagle-import:SOP65P640X120-14N")
      (libsource (lib "eagle-import") (part "MCP3004-I/ST"))
    )
    (comp (ref "U9")
      (value "AD5024BRUZ")
      (footprint "eagle-import:SOP65P640X120-16N")
      (libsource (lib "eagle-import") (part "AD5024BRUZ"))
    )
    (comp (ref "X1")
      (value "22-23-2021")
      (footprint "eagle-import:22-23-2021")
      (fields (field (name "MF") "MOLEX"))
      (libsource (lib "eagle-import") (part "22-23-2021"))
    )
  )
  (nets
    (net (code "1") (name "3.3V") (class "Default")
      (node (ref "C10") (pin "2") (pinfunction "P$2_2") (pintype "passive"))
      (node (ref "C18") (pin "2") (pinfunction "P$2_2") (pintype "passive"))
      (node (ref "C19") (pin "2") (pinfunction "P$2_2") (pintype "passive"))
      (node (ref "C2") (pin "+") (pinfunction "+_+") (pintype "passive"))
      (node (ref "C20") (pin "2") (pinfunction "P$2_2") (pintype "passive"))
      (node (ref "C21") (pin "2") (pinfunction "P$2_2") (pintype "passive"))
      (node (ref "C22") (pin "2") (pinfunction "P$2_2") (pintype "passive"))
      (node (ref "C23") (pin "2") (pinfunction "P$2_2") (pintype "passive"))
      (node (ref "C24") (pin "2") (pinfunction "P$2_2") (pintype "passive"))
      (node (ref "C25") (pin "2") (pinfunction "P$2_2") (pintype "passive"))
      (node (ref "C26") (pin "2") (pinfunction "P$2_2") (pintype "passive"))
      (node (ref "C27") (pin "2") (pinfunction "P$2_2") (pintype "passive"))
      (node (ref "C28") (pin "2") (pinfunction "P$2_2") (pintype "passive"))
      (node (ref "C29") (pin "2") (pinfunction "P$2_2") (pintype "passive"))
      (node (ref "C3") (pin "1") (pinfunction "P$1_1") (pintype "passive"))
      (node (ref "C30") (pin "2") (pinfunction "P$2_2") (pintype "passive"))
      (node (ref "C31") (pin "2") (pinfunction "P$2_2") (pintype "passive"))
      (node (ref "C4") (pin "1") (pinfunction "P$1_1") (pintype "passive"))
      (node (ref "C40") (pin "1") (pinfunction "P$1_1") (pintype "passive"))
      (node (ref "C6") (pin "2") (pinfunction "P$2_2") (pintype "passive"))
      (node (ref "J1") (pin "D3") (pinfunction "D_D3") (pintype "bidirectional"))
      (node (ref "J1") (pin "D4") (pinfunction "D_D4") (pintype "bidirectional"))
      (node (ref "J1") (pin "G4") (pinfunction "G_G4") (pintype "bidirectional"))
      (node (ref "J2") (pin "H4") (pinfunction "H_H4") (pintype "bidirectional"))
      (node (ref "J2") (pin "J4") (pinfunction "J_J4") (pintype "bidirectional"))
      (node (ref "J2") (pin "K1") (pinfunction "K_K1") (pintype "bidirectional"))
      (node (ref "J2") (pin "K2") (pinfunction "K_K2") (pintype "bidirectional"))
      (node (ref "J2") (pin "K3") (pinfunction "K_K3") (pintype "bidirectional"))
      (node (ref "J2") (pin "K4") (pinfunction "K_K4") (pintype "bidirectional"))
      (node (ref "L1") (pin "2") (pinfunction "2_2") (pintype "passive"))
      (node (ref "R12") (pin "1") (pinfunction "1_1") (pintype "passive"))
      (node (ref "R13") (pin "1") (pinfunction "1_1") (pintype "passive"))
      (node (ref "R15") (pin "1") (pinfunction "1_1") (pintype "passive"))
      (node (ref "R19") (pin "1") (pinfunction "1_1") (pintype "passive"))
      (node (ref "R2") (pin "1") (pinfunction "1_1") (pintype "passive"))
      (node (ref "R22") (pin "1") (pinfunction "1_1") (pintype "passive"))
      (node (ref "R24") (pin "1") (pinfunction "1_1") (pintype "passive"))
      (node (ref "R25") (pin "1") (pinfunction "1_1") (pintype "passive"))
      (node (ref "R32") (pin "1") (pinfunction "1_1") (pintype "passive"))
      (node (ref "R33") (pin "2") (pinfunction "2_2") (pintype "passive"))
      (node (ref "R34") (pin "2") (pinfunction "2_2") (pintype "passive"))
      (node (ref "R35") (pin "1") (pinfunction "1_1") (pintype "passive"))
      (node (ref "R36") (pin "1") (pinfunction "1_1") (pintype "passive"))
      (node (ref "R37") (pin "1") (pinfunction "1_1") (pintype "passive"))
      (node (ref "R38") (pin "1") (pinfunction "1_1") (pintype "passive"))
      (node (ref "R60") (pin "1") (pinfunction "1_1") (pintype "passive"))
      (node (ref "R61") (pin "1") (pinfunction "1_1") (pintype "passive"))
      (node (ref "R62") (pin "1") (pinfunction "1_1") (pintype "passive"))
      (node (ref "TP3") (pin "P$1") (pinfunction "P$1_P$1") (pintype "bidirectional"))
      (node (ref "U$1") (pin "P$43") (pinfunction "VCC1_P$43") (pintype "bidirectional"))
      (node (ref "U$1") (pin "P$44") (pinfunction "VCC2_P$44") (pintype "bidirectional"))
      (node (ref "U$19") (pin "5") (pinfunction "VDD_5") (pintype "power_in"))
      (node (ref "U$24") (pin "5") (pinfunction "VDD_5") (pintype "power_in"))
      (node (ref "U$30") (pin "5") (pinfunction "VDD_5") (pintype "power_in"))
      (node (ref "U$33") (pin "5") (pinfunction "VDD_5") (pintype "power_in"))
      (node (ref "U$34") (pin "5") (pinfunction "VDD_5") (pintype "power_in"))
      (node (ref "U$37") (pin "5") (pinfunction "VDD_5") (pintype "power_in"))
      (node (ref "U$39") (pin "5") (pinfunction "VDD_5") (pintype "power_in"))
      (node (ref "U$40") (pin "5") (pinfunction "VDD_5") (pintype "power_in"))
      (node (ref "U$43") (pin "5") (pinfunction "VDD_5") (pintype "power_in"))
      (node (ref "U$45") (pin "5") (pinfunction "VDD_5") (pintype "power_in"))
      (node (ref "U$47") (pin "5") (pinfunction "VDD_5") (pintype "power_in"))
      (node (ref "U$49") (pin "5") (pinfunction "VDD_5") (pintype "power_in"))
      (node (ref "U$55") (pin "5") (pinfunction "VDD_5") (pintype "power_in"))
      (node (ref "U$57") (pin "5") (pinfunction "VDD_5") (pintype "power_in"))
      (node (ref "U$59") (pin "5") (pinfunction "VDD_5") (pintype "power_in"))
      (node (ref "U1") (pin "3") (pinfunction "VCC_3") (pintype "power_in"))
      (node (ref "U2") (pin "16") (pinfunction "VCC_16") (pintype "power_in"))
      (node (ref "U4") (pin "10") (pinfunction "OE_10") (pintype "bidirectional"))
      (node (ref "U4") (pin "2") (pinfunction "VCCA_2") (pintype "bidirectional"))
      (node (ref "U7") (pin "1") (pinfunction "VDD_1") (pintype "power_in"))
      (node (ref "U8") (pin "13") (pinfunction "VREF_13") (pintype "input"))
      (node (ref "U8") (pin "14") (pinfunction "VDD_14") (pintype "power_in"))
    )
    (net (code "2") (name "5.0V") (class "Default")
      (node (ref "C1") (pin "2") (pinfunction "P$2_2") (pintype "passive"))
      (node (ref "C13") (pin "1") (pinfunction "P$1_1") (pintype "passive"))
      (node (ref "C17") (pin "2") (pinfunction "P$2_2") (pintype "passive"))
      (node (ref "C38") (pin "1") (pinfunction "P$1_1") (pintype "passive"))
      (node (ref "C39") (pin "1") (pinfunction "P$1_1") (pintype "passive"))
      (node (ref "IC5") (pin "2") (pinfunction "VOUT_2") (pintype "output"))
      (node (ref "R44") (pin "2") (pinfunction "2_2") (pintype "passive"))
      (node (ref "R45") (pin "2") (pinfunction "2_2") (pintype "passive"))
      (node (ref "R46") (pin "2") (pinfunction "2_2") (pintype "passive"))
      (node (ref "R47") (pin "2") (pinfunction "2_2") (pintype "passive"))
      (node (ref "R63") (pin "1") (pinfunction "1_1") (pintype "passive"))
      (node (ref "R64") (pin "1") (pinfunction "1_1") (pintype "passive"))
      (node (ref "R65") (pin "1") (pinfunction "1_1") (pintype "passive"))
      (node (ref "TP2") (pin "P$1") (pinfunction "P$1_P$1") (pintype "bidirectional"))
      (node (ref "U4") (pin "19") (pinfunction "VCCB_19") (pintype "bidirectional"))
      (node (ref "U5") (pin "14") (pinfunction "VCC_14") (pintype "power_in"))
      (node (ref "U6") (pin "14") (pinfunction "VCC_14") (pintype "power_in"))
      (node (ref "U9") (pin "11") (pinfunction "VREFD_11") (pintype "input"))
      (node (ref "U9") (pin "3") (pinfunction "VDD_3") (pintype "power_in"))
      (node (ref "U9") (pin "4") (pinfunction "VREFB_4") (pintype "input"))
      (node (ref "U9") (pin "5") (pinfunction "VREFA_5") (pintype "input"))
      (node (ref "U9") (pin "9") (pinfunction "VREFC_9") (pintype "input"))
    )
    (net (code "3") (name "12V") (class "Default")
      (node (ref "C16") (pin "2") (pinfunction "P$2_2") (pintype "passive"))
      (node (ref "C7") (pin "+") (pinfunction "+_+") (pintype "passive"))
      (node (ref "IC2") (pin "1") (pinfunction "IN_1") (pintype "input"))
      (node (ref "IC5") (pin "3") (pinfunction "VIN_3") (pintype "input"))
      (node (ref "J1") (pin "A4") (pinfunction "A_A4") (pintype "bidirectional"))
      (node (ref "PTC2") (pin "P$1") (pinfunction "1_P$1") (pintype "passive"))
      (node (ref "TP1") (pin "P$1") (pinfunction "P$1_P$1") (pintype "bidirectional"))
      (node (ref "X1") (pin "1") (pinfunction "S_1") (pintype "passive"))
    )
    (net (code "4") (name "ADC_CS") (class "Default")
      (node (ref "U$1") (pin "P$12") (pinfunction "PE9_P$12") (pintype "bidirectional"))
      (node (ref "U8") (pin "8") (pinfunction "*CS/SHDN_8") (pintype "input"))
    )
    (net (code "5") (name "AUX2") (class "Default")
      (node (ref "J1") (pin "E1") (pinfunction "E_E1") (pintype "bidirectional"))
      (node (ref "S2") (pin "2") (pinfunction "P_2") (pintype "passive"))
    )
    (net (code "6") (name "AUX2I") (class "Default")
      (node (ref "R60") (pin "2") (pinfunction "2_2") (pintype "passive"))
      (node (ref "S2") (pin "1") (pinfunction "O_1") (pintype "passive"))
      (node (ref "U$1") (pin "P$17") (pinfunction "PE14_P$17") (pintype "bidirectional"))
    )
    (net (code "7") (name "AUX3") (class "Default")
      (node (ref "J1") (pin "E2") (pinfunction "E_E2") (pintype "bidirectional"))
      (node (ref "S3") (pin "2") (pinfunction "P_2") (pintype "passive"))
    )
    (net (code "8") (name "AUX3I") (class "Default")
      (node (ref "R61") (pin "2") (pinfunction "2_2") (pintype "passive"))
      (node (ref "S3") (pin "1") (pinfunction "O_1") (pintype "passive"))
      (node (ref "U$1") (pin "P$18") (pinfunction "PE15_P$18") (pintype "bidirectional"))
    )
    (net (code "9") (name "AUX4") (class "Default")
      (node (ref "J1") (pin "E3") (pinfunction "E_E3") (pintype "bidirectional"))
      (node (ref "S4") (pin "2") (pinfunction "P_2") (pintype "passive"))
    )
    (net (code "10") (name "AUX4I") (class "Default")
      (node (ref "R62") (pin "2") (pinfunction "2_2") (pintype "passive"))
      (node (ref "S4") (pin "1") (pinfunction "O_1") (pintype "passive"))
      (node (ref "U$1") (pin "P$21") (pinfunction "PB10_P$21") (pintype "bidirectional"))
    )
    (net (code "11") (name "AUX5") (class "Default")
      (node (ref "J1") (pin "E4") (pinfunction "E_E4") (pintype "bidirectional"))
      (node (ref "U$1") (pin "P$22") (pinfunction "PB11_P$22") (pintype "bidirectional"))
    )
    (net (code "12") (name "AUX6") (class "Default")
      (node (ref "J2") (pin "E1") (pinfunction "E_E1") (pintype "bidirectional"))
      (node (ref "U$1") (pin "P$65") (pinfunction "PE4_P$65") (pintype "bidirectional"))
    )
    (net (code "13") (name "AUX7") (class "Default")
      (node (ref "J2") (pin "E3") (pinfunction "E_E3") (pintype "bidirectional"))
      (node (ref "U$1") (pin "P$66") (pinfunction "PE5_P$66") (pintype "bidirectional"))
    )
    (net (code "14") (name "BITE") (class "Default")
      (node (ref "J1") (pin "A1") (pinfunction "A_A1") (pintype "bidirectional"))
      (node (ref "Q11") (pin "3") (pinfunction "C_3") (pintype "passive"))
      (node (ref "R65") (pin "2") (pinfunction "2_2") (pintype "passive"))
    )
    (net (code "15") (name "BITEL") (class "Default")
      (node (ref "Q11") (pin "2") (pinfunction "E_2") (pintype "passive"))
      (node (ref "U$1") (pin "P$13") (pinfunction "PE10_P$13") (pintype "bidirectional"))
    )
    (net (code "16") (name "BRAKE-POT") (class "Default")
      (node (ref "J1") (pin "C3") (pinfunction "C_C3") (pintype "bidirectional"))
      (node (ref "U$57") (pin "3") (pinfunction "VIN+_3") (pintype "input"))
    )
    (net (code "17") (name "BRAKE-POTB") (class "Default")
      (node (ref "U$1") (pin "P$8") (pinfunction "PB0_P$8") (pintype "bidirectional"))
      (node (ref "U$57") (pin "1") (pinfunction "VOUT_1") (pintype "output"))
      (node (ref "U$57") (pin "4") (pinfunction "VIN-_4") (pintype "input"))
    )
    (net (code "18") (name "BRAKEP") (class "Default")
      (node (ref "J2") (pin "F4") (pinfunction "F_F4") (pintype "bidirectional"))
      (node (ref "R19") (pin "2") (pinfunction "2_2") (pintype "passive"))
      (node (ref "U$39") (pin "3") (pinfunction "VIN+_3") (pintype "input"))
    )
    (net (code "19") (name "BRAKEP2") (class "Default")
      (node (ref "J2") (pin "F2") (pinfunction "F_F2") (pintype "bidirectional"))
      (node (ref "R15") (pin "2") (pinfunction "2_2") (pintype "passive"))
      (node (ref "U$43") (pin "3") (pinfunction "VIN+_3") (pintype "input"))
    )
    (net (code "20") (name "BRAKEP2B") (class "Default")
      (node (ref "U$1") (pin "P$76") (pinfunction "PA1_P$76") (pintype "bidirectional"))
      (node (ref "U$43") (pin "1") (pinfunction "VOUT_1") (pintype "output"))
      (node (ref "U$43") (pin "4") (pinfunction "VIN-_4") (pintype "input"))
    )
    (net (code "21") (name "BRAKEPB") (class "Default")
      (node (ref "U$1") (pin "P$75") (pinfunction "PA0_P$75") (pintype "bidirectional"))
      (node (ref "U$39") (pin "1") (pinfunction "VOUT_1") (pintype "output"))
      (node (ref "U$39") (pin "4") (pinfunction "VIN-_4") (pintype "input"))
    )
    (net (code "22") (name "CANH") (class "Default")
      (node (ref "J2") (pin "D2") (pinfunction "D_D2") (pintype "bidirectional"))
      (node (ref "R7") (pin "1") (pinfunction "1_1") (pintype "passive"))
      (node (ref "U1") (pin "6") (pinfunction "CANL_6") (pintype "input"))
    )
    (net (code "23") (name "CANL") (class "Default")
      (node (ref "J2") (pin "D1") (pinfunction "D_D1") (pintype "bidirectional"))
      (node (ref "R3") (pin "1") (pinfunction "1_1") (pintype "passive"))
      (node (ref "U1") (pin "7") (pinfunction "CANH_7") (pintype "input"))
    )
    (net (code "24") (name "CAN_RX") (class "Default")
      (node (ref "U$1") (pin "P$55") (pinfunction "PB5_P$55") (pintype "bidirectional"))
      (node (ref "U1") (pin "4") (pinfunction "RXD_4") (pintype "output"))
    )
    (net (code "25") (name "CAN_TX") (class "Default")
      (node (ref "U$1") (pin "P$56") (pinfunction "PB6_P$56") (pintype "bidirectional"))
      (node (ref "U1") (pin "1") (pinfunction "TXD_1") (pintype "input"))
    )
    (net (code "26") (name "CLUTCH-POT") (class "Default")
      (node (ref "J1") (pin "C4") (pinfunction "C_C4") (pintype "bidirectional"))
      (node (ref "U$59") (pin "3") (pinfunction "VIN+_3") (pintype "input"))
    )
    (net (code "27") (name "CLUTCH-POTB") (class "Default")
      (node (ref "U$1") (pin "P$9") (pinfunction "PB1_P$9") (pintype "bidirectional"))
      (node (ref "U$59") (pin "1") (pinfunction "VOUT_1") (pintype "output"))
      (node (ref "U$59") (pin "4") (pinfunction "VIN-_4") (pintype "input"))
    )
    (net (code "28") (name "COMRX") (class "Default")
      (node (ref "U$1") (pin "P$52") (pinfunction "PD6_P$52") (pintype "bidirectional"))
      (node (ref "U2") (pin "9") (pinfunction "R2OUT_9") (pintype "output"))
    )
    (net (code "29") (name "COMTX") (class "Default")
      (node (ref "U$1") (pin "P$51") (pinfunction "PD5_P$51") (pintype "bidirectional"))
      (node (ref "U2") (pin "10") (pinfunction "T2IN_10") (pintype "input"))
    )
    (net (code "30") (name "DACCLR") (class "Default")
      (node (ref "U$1") (pin "P$23") (pinfunction "PB12_P$23") (pintype "bidirectional"))
      (node (ref "U9") (pin "10") (pinfunction "CLR*_10") (pintype "input"))
    )
    (net (code "31") (name "DACCS") (class "Default")
      (node (ref "U$1") (pin "P$28") (pinfunction "PD9_P$28") (pintype "bidirectional"))
      (node (ref "U9") (pin "2") (pinfunction "SYNC*_2") (pintype "input"))
    )
    (net (code "32") (name "ECU1") (class "Default")
      (node (ref "J2") (pin "C4") (pinfunction "C_C4") (pintype "bidirectional"))
      (node (ref "Q1") (pin "3") (pinfunction "C_3") (pintype "passive"))
      (node (ref "R64") (pin "2") (pinfunction "2_2") (pintype "passive"))
    )
    (net (code "33") (name "ECU1L") (class "Default")
      (node (ref "Q1") (pin "2") (pinfunction "E_2") (pintype "passive"))
      (node (ref "U$1") (pin "P$67") (pinfunction "PE6_P$67") (pintype "bidirectional"))
    )
    (net (code "34") (name "ECU2") (class "Default")
      (node (ref "J2") (pin "D4") (pinfunction "D_D4") (pintype "bidirectional"))
      (node (ref "Q2") (pin "3") (pinfunction "C_3") (pintype "passive"))
      (node (ref "R63") (pin "2") (pinfunction "2_2") (pintype "passive"))
    )
    (net (code "35") (name "ECU2L") (class "Default")
      (node (ref "Q2") (pin "2") (pinfunction "E_2") (pintype "passive"))
      (node (ref "U$1") (pin "P$68") (pinfunction "PC13_P$68") (pintype "bidirectional"))
    )
    (net (code "36") (name "ENCODER1") (class "Default")
      (node (ref "C32") (pin "1") (pinfunction "P$1_1") (pintype "passive"))
      (node (ref "J1") (pin "G2") (pinfunction "G_G2") (pintype "bidirectional"))
      (node (ref "R35") (pin "2") (pinfunction "2_2") (pintype "passive"))
      (node (ref "U$1") (pin "P$14") (pinfunction "PE11_P$14") (pintype "bidirectional"))
    )
    (net (code "37") (name "ENCODER2") (class "Default")
      (node (ref "C33") (pin "1") (pinfunction "P$1_1") (pintype "passive"))
      (node (ref "J1") (pin "G3") (pinfunction "G_G3") (pintype "bidirectional"))
      (node (ref "R36") (pin "2") (pinfunction "2_2") (pintype "passive"))
      (node (ref "U$1") (pin "P$15") (pinfunction "PE12_P$15") (pintype "bidirectional"))
    )
    (net (code "38") (name "FUELTEMP") (class "Default")
      (node (ref "J1") (pin "C2") (pinfunction "C_C2") (pintype "bidirectional"))
      (node (ref "R22") (pin "2") (pinfunction "2_2") (pintype "passive"))
      (node (ref "U$55") (pin "3") (pinfunction "VIN+_3") (pintype "input"))
    )
    (net (code "39") (name "FUELTEMPB") (class "Default")
      (node (ref "U$1") (pin "P$7") (pinfunction "PC5_P$7") (pintype "bidirectional"))
      (node (ref "U$55") (pin "1") (pinfunction "VOUT_1") (pintype "output"))
      (node (ref "U$55") (pin "4") (pinfunction "VIN-_4") (pintype "input"))
    )
    (net (code "40") (name "GEARPOSAN") (class "Default")
      (node (ref "J2") (pin "H3") (pinfunction "H_H3") (pintype "bidirectional"))
      (node (ref "U$49") (pin "3") (pinfunction "VIN+_3") (pintype "input"))
    )
    (net (code "41") (name "GEARPOSANB") (class "Default")
      (node (ref "U$1") (pin "P$71") (pinfunction "PC0_P$71") (pintype "bidirectional"))
      (node (ref "U$49") (pin "1") (pinfunction "VOUT_1") (pintype "output"))
      (node (ref "U$49") (pin "4") (pinfunction "VIN-_4") (pintype "input"))
    )
    (net (code "42") (name "GND") (class "Default")
      (node (ref "C1") (pin "1") (pinfunction "P$1_1") (pintype "passive"))
      (node (ref "C10") (pin "1") (pinfunction "P$1_1") (pintype "passive"))
      (node (ref "C11") (pin "2") (pinfunction "P$2_2") (pintype "passive"))
      (node (ref "C12") (pin "1") (pinfunction "P$1_1") (pintype "passive"))
      (node (ref "C13") (pin "2") (pinfunction "P$2_2") (pintype "passive"))
      (node (ref "C16") (pin "1") (pinfunction "P$1_1") (pintype "passive"))
      (node (ref "C17") (pin "1") (pinfunction "P$1_1") (pintype "passive"))
      (node (ref "C18") (pin "1") (pinfunction "P$1_1") (pintype "passive"))
      (node (ref "C19") (pin "1") (pinfunction "P$1_1") (pintype "passive"))
      (node (ref "C2") (pin "-") (pinfunction "-_-") (pintype "passive"))
      (node (ref "C20") (pin "1") (pinfunction "P$1_1") (pintype "passive"))
      (node (ref "C21") (pin "1") (pinfunction "P$1_1") (pintype "passive"))
      (node (ref "C22") (pin "1") (pinfunction "P$1_1") (pintype "passive"))
      (node (ref "C23") (pin "1") (pinfunction "P$1_1") (pintype "passive"))
      (node (ref "C24") (pin "1") (pinfunction "P$1_1") (pintype "passive"))
      (node (ref "C25") (pin "1") (pinfunction "P$1_1") (pintype "passive"))
      (node (ref "C26") (pin "1") (pinfunction "P$1_1") (pintype "passive"))
      (node (ref "C27") (pin "1") (pinfunction "P$1_1") (pintype "passive"))
      (node (ref "C28") (pin "1") (pinfunction "P$1_1") (pintype "passive"))
      (node (ref "C29") (pin "1") (pinfunction "P$1_1") (pintype "passive"))
      (node (ref "C3") (pin "2") (pinfunction "P$2_2") (pintype "passive"))
      (node (ref "C30") (pin "1") (pinfunction "P$1_1") (pintype "passive"))
      (node (ref "C31") (pin "1") (pinfunction "P$1_1") (pintype "passive"))
      (node (ref "C32") (pin "2") (pinfunction "P$2_2") (pintype "passive"))
      (node (ref "C33") (pin "2") (pinfunction "P$2_2") (pintype "passive"))
      (node (ref "C38") (pin "2") (pinfunction "P$2_2") (pintype "passive"))
      (node (ref "C39") (pin "2") (pinfunction "P$2_2") (pintype "passive"))
      (node (ref "C4") (pin "2") (pinfunction "P$2_2") (pintype "passive"))
      (node (ref "C40") (pin "2") (pinfunction "P$2_2") (pintype "passive"))
      (node (ref "C5") (pin "2") (pinfunction "P$2_2") (pintype "passive"))
      (node (ref "C6") (pin "1") (pinfunction "P$1_1") (pintype "passive"))
      (node (ref "C7") (pin "-") (pinfunction "-_-") (pintype "passive"))
      (node (ref "D8") (pin "A") (pinfunction "A_A") (pintype "passive"))
      (node (ref "IC2") (pin "3") (pinfunction "GND_3") (pintype "power_in"))
      (node (ref "IC2") (pin "5") (pinfunction "EN_5") (pintype "input"))
      (node (ref "IC2") (pin "6") (pinfunction "GND_6") (pintype "power_in"))
      (node (ref "IC5") (pin "1") (pinfunction "GND_1") (pintype "power_in"))
      (node (ref "J1") (pin "B1") (pinfunction "B_B1") (pintype "bidirectional"))
      (node (ref "J1") (pin "B2") (pinfunction "B_B2") (pintype "bidirectional"))
      (node (ref "J1") (pin "B3") (pinfunction "B_B3") (pintype "bidirectional"))
      (node (ref "J1") (pin "B4") (pinfunction "B_B4") (pintype "bidirectional"))
      (node (ref "J1") (pin "D2") (pinfunction "D_D2") (pintype "bidirectional"))
      (node (ref "J1") (pin "F1") (pinfunction "F_F1") (pintype "bidirectional"))
      (node (ref "J1") (pin "F2") (pinfunction "F_F2") (pintype "bidirectional"))
      (node (ref "J1") (pin "F3") (pinfunction "F_F3") (pintype "bidirectional"))
      (node (ref "J1") (pin "F4") (pinfunction "F_F4") (pintype "bidirectional"))
      (node (ref "J1") (pin "G1") (pinfunction "G_G1") (pintype "bidirectional"))
      (node (ref "J1") (pin "H4") (pinfunction "H_H4") (pintype "bidirectional"))
      (node (ref "J1") (pin "J1") (pinfunction "J_J1") (pintype "bidirectional"))
      (node (ref "J1") (pin "M4") (pinfunction "M_M4") (pintype "bidirectional"))
      (node (ref "J2") (pin "C3") (pinfunction "C_C3") (pintype "bidirectional"))
      (node (ref "J2") (pin "D3") (pinfunction "D_D3") (pintype "bidirectional"))
      (node (ref "J2") (pin "E2") (pinfunction "E_E2") (pintype "bidirectional"))
      (node (ref "J2") (pin "E4") (pinfunction "E_E4") (pintype "bidirectional"))
      (node (ref "J2") (pin "G1") (pinfunction "G_G1") (pintype "bidirectional"))
      (node (ref "J2") (pin "G2") (pinfunction "G_G2") (pintype "bidirectional"))
      (node (ref "J2") (pin "G3") (pinfunction "G_G3") (pintype "bidirectional"))
      (node (ref "J2") (pin "G4") (pinfunction "G_G4") (pintype "bidirectional"))
      (node (ref "J2") (pin "H2") (pinfunction "H_H2") (pintype "bidirectional"))
      (node (ref "J2") (pin "J2") (pinfunction "J_J2") (pintype "bidirectional"))
      (node (ref "J2") (pin "M1") (pinfunction "M_M1") (pintype "bidirectional"))
      (node (ref "J2") (pin "M2") (pinfunction "M_M2") (pintype "bidirectional"))
      (node (ref "J2") (pin "M3") (pinfunction "M_M3") (pintype "bidirectional"))
      (node (ref "J2") (pin "M4") (pinfunction "M_M4") (pintype "bidirectional"))
      (node (ref "OK1") (pin "2") (pinfunction "C_2") (pintype "passive"))
      (node (ref "OK2") (pin "2") (pinfunction "C_2") (pintype "passive"))
      (node (ref "OK3") (pin "2") (pinfunction "C_2") (pintype "passive"))
      (node (ref "OK4") (pin "2") (pinfunction "C_2") (pintype "passive"))
      (node (ref "OK5") (pin "2") (pinfunction "C_2") (pintype "passive"))
      (node (ref "OK6") (pin "2") (pinfunction "C_2") (pintype "passive"))
      (node (ref "Q3") (pin "2") (pinfunction "E_2") (pintype "passive"))
      (node (ref "R1") (pin "1") (pinfunction "1_1") (pintype "passive"))
      (node (ref "R31") (pin "1") (pinfunction "1_1") (pintype "passive"))
      (node (ref "R5") (pin "1") (pinfunction "1_1") (pintype "passive"))
      (node (ref "R55") (pin "1") (pinfunction "1_1") (pintype "passive"))
      (node (ref "R57") (pin "1") (pinfunction "1_1") (pintype "passive"))
      (node (ref "R59") (pin "1") (pinfunction "1_1") (pintype "passive"))
      (node (ref "R8") (pin "1") (pinfunction "1_1") (pintype "passive"))
      (node (ref "TP4") (pin "P$1") (pinfunction "P$1_P$1") (pintype "bidirectional"))
      (node (ref "U$1") (pin "P$19") (pinfunction "GND1_P$19") (pintype "bidirectional"))
      (node (ref "U$1") (pin "P$20") (pinfunction "GND2_P$20") (pintype "bidirectional"))
      (node (ref "U$1") (pin "P$41") (pinfunction "GND3_P$41") (pintype "bidirectional"))
      (node (ref "U$1") (pin "P$42") (pinfunction "GND4_P$42") (pintype "bidirectional"))
      (node (ref "U$1") (pin "P$62") (pinfunction "GND5_P$62") (pintype "bidirectional"))
      (node (ref "U$1") (pin "P$69") (pinfunction "GND6_P$69") (pintype "bidirectional"))
      (node (ref "U$1") (pin "P$70") (pinfunction "GND7_P$70") (pintype "bidirectional"))
      (node (ref "U$1") (pin "P$78") (pinfunction "GND8_P$78") (pintype "bidirectional"))
      (node (ref "U$19") (pin "2") (pinfunction "VSS_2") (pintype "passive"))
      (node (ref "U$24") (pin "2") (pinfunction "VSS_2") (pintype "passive"))
      (node (ref "U$30") (pin "2") (pinfunction "VSS_2") (pintype "passive"))
      (node (ref "U$33") (pin "2") (pinfunction "VSS_2") (pintype "passive"))
      (node (ref "U$34") (pin "2") (pinfunction "VSS_2") (pintype "passive"))
      (node (ref "U$37") (pin "2") (pinfunction "VSS_2") (pintype "passive"))
      (node (ref "U$39") (pin "2") (pinfunction "VSS_2") (pintype "passive"))
      (node (ref "U$40") (pin "2") (pinfunction "VSS_2") (pintype "passive"))
      (node (ref "U$43") (pin "2") (pinfunction "VSS_2") (pintype "passive"))
      (node (ref "U$45") (pin "2") (pinfunction "VSS_2") (pintype "passive"))
      (node (ref "U$47") (pin "2") (pinfunction "VSS_2") (pintype "passive"))
      (node (ref "U$49") (pin "2") (pinfunction "VSS_2") (pintype "passive"))
      (node (ref "U$55") (pin "2") (pinfunction "VSS_2") (pintype "passive"))
      (node (ref "U$57") (pin "2") (pinfunction "VSS_2") (pintype "passive"))
      (node (ref "U$59") (pin "2") (pinfunction "VSS_2") (pintype "passive"))
      (node (ref "U1") (pin "2") (pinfunction "GND_2") (pintype "passive"))
      (node (ref "U1") (pin "8") (pinfunction "RS_8") (pintype "input"))
      (node (ref "U2") (pin "15") (pinfunction "GND_15") (pintype "passive"))
      (node (ref "U4") (pin "11") (pinfunction "GND_11") (pintype "bidirectional"))
      (node (ref "U5") (pin "1") (pinfunction "IN_THRS1_1") (pintype "input"))
      (node (ref "U5") (pin "11") (pinfunction "GND_11") (pintype "passive"))
      (node (ref "U5") (pin "13") (pinfunction "OUT1_13") (pintype "output"))
      (node (ref "U5") (pin "3") (pinfunction "BIAS_3") (pintype "input"))
      (node (ref "U5") (pin "6") (pinfunction "BIAS2_6") (pintype "input"))
      (node (ref "U5") (pin "8") (pinfunction "INT_THRS2_8") (pintype "input"))
      (node (ref "U6") (pin "1") (pinfunction "IN_THRS1_1") (pintype "input"))
      (node (ref "U6") (pin "11") (pinfunction "GND_11") (pintype "passive"))
      (node (ref "U6") (pin "13") (pinfunction "OUT1_13") (pintype "output"))
      (node (ref "U6") (pin "3") (pinfunction "BIAS_3") (pintype "input"))
      (node (ref "U6") (pin "6") (pinfunction "BIAS2_6") (pintype "input"))
      (node (ref "U6") (pin "8") (pinfunction "INT_THRS2_8") (pintype "input"))
      (node (ref "U7") (pin "8") (pinfunction "VSS_8") (pintype "power_in"))
      (node (ref "U8") (pin "12") (pinfunction "AGND_12") (pintype "passive"))
      (node (ref "U8") (pin "7") (pinfunction "DGND_7") (pintype "passive"))
      (node (ref "U9") (pin "1") (pinfunction "LDAC*_1") (pintype "passive"))
      (node (ref "U9") (pin "14") (pinfunction "GND_14") (pintype "passive"))
      (node (ref "U9") (pin "8") (pinfunction "POR_8") (pintype "passive"))
      (node (ref "X1") (pin "2") (pinfunction "S_2") (pintype "passive"))
    )
    (net (code "43") (name "GND-RELAY") (class "Default")
      (node (ref "D1") (pin "A") (pinfunction "A_A") (pintype "passive"))
      (node (ref "D3") (pin "A") (pinfunction "A_A") (pintype "passive"))
      (node (ref "D4") (pin "A") (pinfunction "A_A") (pintype "passive"))
      (node (ref "D5") (pin "A") (pinfunction "A_A") (pintype "passive"))
      (node (ref "D6") (pin "A") (pinfunction "A_A") (pintype "passive"))
      (node (ref "D7") (pin "A") (pinfunction "A_A") (pintype "passive"))
      (node (ref "J1") (pin "K1") (pinfunction "K_K1") (pintype "bidirectional"))
      (node (ref "OK1") (pin "4") (pinfunction "EMI_4") (pintype "passive"))
      (node (ref "OK2") (pin "4") (pinfunction "EMI_4") (pintype "passive"))
      (node (ref "OK3") (pin "4") (pinfunction "EMI_4") (pintype "passive"))
      (node (ref "OK4") (pin "4") (pinfunction "EMI_4") (pintype "passive"))
      (node (ref "OK5") (pin "4") (pinfunction "EMI_4") (pintype "passive"))
      (node (ref "OK6") (pin "4") (pinfunction "EMI_4") (pintype "passive"))
      (node (ref "R10") (pin "2") (pinfunction "2_2") (pintype "passive"))
      (node (ref "R16") (pin "2") (pinfunction "2_2") (pintype "passive"))
      (node (ref "R20") (pin "2") (pinfunction "2_2") (pintype "passive"))
      (node (ref "R23") (pin "2") (pinfunction "2_2") (pintype "passive"))
      (node (ref "R28") (pin "2") (pinfunction "2_2") (pintype "passive"))
      (node (ref "R9") (pin "2") (pinfunction "2_2") (pintype "passive"))
    )
    (net (code "44") (name "GSENS") (class "Default")
      (node (ref "J1") (pin "A2") (pinfunction "A_A2") (pintype "bidirectional"))
      (node (ref "R4") (pin "2") (pinfunction "2_2") (pintype "passive"))
    )
    (net (code "45") (name "GSENSO") (class "Default")
      (node (ref "R33") (pin "1") (pinfunction "1_1") (pintype "passive"))
      (node (ref "U$1") (pin "P$5") (pinfunction "PA7_P$5") (pintype "bidirectional"))
      (node (ref "U$24") (pin "1") (pinfunction "VOUT_1") (pintype "output"))
      (node (ref "U$24") (pin "4") (pinfunction "VIN-_4") (pintype "input"))
    )
    (net (code "46") (name "HB1-DIR") (class "Default")
      (node (ref "U$1") (pin "P$29") (pinfunction "PD10_P$29") (pintype "bidirectional"))
      (node (ref "U4") (pin "6") (pinfunction "A5_6") (pintype "bidirectional"))
    )
    (net (code "47") (name "HB1-DIR-IN") (class "Default")
      (node (ref "J1") (pin "J4") (pinfunction "J_J4") (pintype "bidirectional"))
      (node (ref "U4") (pin "15") (pinfunction "B5_15") (pintype "bidirectional"))
    )
    (net (code "48") (name "HB1-EN") (class "Default")
      (node (ref "U$1") (pin "P$30") (pinfunction "PD11_P$30") (pintype "bidirectional"))
      (node (ref "U4") (pin "7") (pinfunction "A6_7") (pintype "bidirectional"))
    )
    (net (code "49") (name "HB1-EN-IN") (class "Default")
      (node (ref "J1") (pin "H1") (pinfunction "H_H1") (pintype "bidirectional"))
      (node (ref "U4") (pin "14") (pinfunction "B6_14") (pintype "bidirectional"))
    )
    (net (code "50") (name "HB1-PWM") (class "Default")
      (node (ref "U$1") (pin "P$32") (pinfunction "PD13_P$32") (pintype "bidirectional"))
      (node (ref "U4") (pin "5") (pinfunction "A4_5") (pintype "bidirectional"))
    )
    (net (code "51") (name "HB1-PWM-IN") (class "Default")
      (node (ref "J1") (pin "J3") (pinfunction "J_J3") (pintype "bidirectional"))
      (node (ref "U4") (pin "16") (pinfunction "B4_16") (pintype "bidirectional"))
    )
    (net (code "52") (name "HB2-DIR") (class "Default")
      (node (ref "U$1") (pin "P$34") (pinfunction "PD15_P$34") (pintype "bidirectional"))
      (node (ref "U4") (pin "3") (pinfunction "A2_3") (pintype "bidirectional"))
    )
    (net (code "53") (name "HB2-DIR-IN") (class "Default")
      (node (ref "J1") (pin "K4") (pinfunction "K_K4") (pintype "bidirectional"))
      (node (ref "U4") (pin "18") (pinfunction "B2_18") (pintype "bidirectional"))
    )
    (net (code "54") (name "HB2-EN") (class "Default")
      (node (ref "U$1") (pin "P$33") (pinfunction "PD14_P$33") (pintype "bidirectional"))
      (node (ref "U4") (pin "1") (pinfunction "A1_1") (pintype "bidirectional"))
    )
    (net (code "55") (name "HB2-EN-IN") (class "Default")
      (node (ref "J1") (pin "K3") (pinfunction "K_K3") (pintype "bidirectional"))
      (node (ref "U4") (pin "20") (pinfunction "B1_20") (pintype "bidirectional"))
    )
    (net (code "56") (name "HB2-PWM") (class "Default")
      (node (ref "U$1") (pin "P$31") (pinfunction "PD12_P$31") (pintype "bidirectional"))
      (node (ref "U4") (pin "4") (pinfunction "A3_4") (pintype "bidirectional"))
    )
    (net (code "57") (name "HB2-PWM-IN") (class "Default")
      (node (ref "J1") (pin "J2") (pinfunction "J_J2") (pintype "bidirectional"))
      (node (ref "U4") (pin "17") (pinfunction "B3_17") (pintype "bidirectional"))
    )
    (net (code "58") (name "IGNCUT") (class "Default")
      (node (ref "R17") (pin "2") (pinfunction "2_2") (pintype "passive"))
      (node (ref "U$1") (pin "P$10") (pinfunction "PE7_P$10") (pintype "bidirectional"))
    )
    (net (code "59") (name "IGNCUTO") (class "Default")
      (node (ref "J2") (pin "H1") (pinfunction "H_H1") (pintype "bidirectional"))
      (node (ref "Q3") (pin "3") (pinfunction "C_3") (pintype "passive"))
    )
    (net (code "60") (name "MISO") (class "Default")
      (node (ref "JP1") (pin "1") (pinfunction "1_1") (pintype "passive"))
      (node (ref "U$1") (pin "P$25") (pinfunction "PB14_P$25") (pintype "bidirectional"))
      (node (ref "U8") (pin "10") (pinfunction "DOUT_10") (pintype "output"))
    )
    (net (code "61") (name "MOSI") (class "Default")
      (node (ref "JP1") (pin "2") (pinfunction "2_2") (pintype "passive"))
      (node (ref "U$1") (pin "P$26") (pinfunction "PB15_P$26") (pintype "bidirectional"))
      (node (ref "U8") (pin "9") (pinfunction "DIN_9") (pintype "input"))
      (node (ref "U9") (pin "15") (pinfunction "DIN_15") (pintype "input"))
    )
    (net (code "62") (name "NEUTRAL") (class "Default")
      (node (ref "J2") (pin "J1") (pinfunction "J_J1") (pintype "bidirectional"))
      (node (ref "R37") (pin "2") (pinfunction "2_2") (pintype "passive"))
      (node (ref "U$1") (pin "P$11") (pinfunction "PE8_P$11") (pintype "bidirectional"))
    )
    (net (code "63") (name "Net-(C5-P$1)") (class "Default")
      (node (ref "C5") (pin "1") (pinfunction "P$1_1") (pintype "passive"))
      (node (ref "R3") (pin "2") (pinfunction "2_2") (pintype "passive"))
      (node (ref "R7") (pin "2") (pinfunction "2_2") (pintype "passive"))
      (node (ref "U1") (pin "5") (pinfunction "SPLIT_5") (pintype "output"))
    )
    (net (code "64") (name "Net-(C8-P$1)") (class "Default")
      (node (ref "C8") (pin "1") (pinfunction "P$1_1") (pintype "passive"))
      (node (ref "U2") (pin "1") (pinfunction "C1+_1") (pintype "input"))
    )
    (net (code "65") (name "Net-(C8-P$2)") (class "Default")
      (node (ref "C8") (pin "2") (pinfunction "P$2_2") (pintype "passive"))
      (node (ref "U2") (pin "3") (pinfunction "C1-_3") (pintype "input"))
    )
    (net (code "66") (name "Net-(C9-P$1)") (class "Default")
      (node (ref "C9") (pin "1") (pinfunction "P$1_1") (pintype "passive"))
      (node (ref "U2") (pin "4") (pinfunction "C2+_4") (pintype "input"))
    )
    (net (code "67") (name "Net-(C9-P$2)") (class "Default")
      (node (ref "C9") (pin "2") (pinfunction "P$2_2") (pintype "passive"))
      (node (ref "U2") (pin "5") (pinfunction "C2-_5") (pintype "input"))
    )
    (net (code "68") (name "Net-(C11-P$1)") (class "Default")
      (node (ref "C11") (pin "1") (pinfunction "P$1_1") (pintype "passive"))
      (node (ref "U2") (pin "2") (pinfunction "V+_2") (pintype "power_in"))
    )
    (net (code "69") (name "Net-(C12-P$2)") (class "Default")
      (node (ref "C12") (pin "2") (pinfunction "P$2_2") (pintype "passive"))
      (node (ref "U2") (pin "6") (pinfunction "V-_6") (pintype "power_in"))
    )
    (net (code "70") (name "Net-(C34-P$1)") (class "Default")
      (node (ref "C34") (pin "1") (pinfunction "P$1_1") (pintype "passive"))
      (node (ref "R27") (pin "2") (pinfunction "2_2") (pintype "passive"))
      (node (ref "R40") (pin "2") (pinfunction "2_2") (pintype "passive"))
      (node (ref "U5") (pin "16") (pinfunction "IN1+_16") (pintype "input"))
    )
    (net (code "71") (name "Net-(C34-P$2)") (class "Default")
      (node (ref "C34") (pin "2") (pinfunction "P$2_2") (pintype "passive"))
      (node (ref "R39") (pin "2") (pinfunction "2_2") (pintype "passive"))
      (node (ref "R40") (pin "1") (pinfunction "1_1") (pintype "passive"))
      (node (ref "U5") (pin "15") (pinfunction "IN1-_15") (pintype "input"))
    )
    (net (code "72") (name "Net-(C35-P$1)") (class "Default")
      (node (ref "C35") (pin "1") (pinfunction "P$1_1") (pintype "passive"))
      (node (ref "R41") (pin "2") (pinfunction "2_2") (pintype "passive"))
      (node (ref "R43") (pin "2") (pinfunction "2_2") (pintype "passive"))
      (node (ref "U5") (pin "9") (pinfunction "IN2+_9") (pintype "input"))
    )
    (net (code "73") (name "Net-(C35-P$2)") (class "Default")
      (node (ref "C35") (pin "2") (pinfunction "P$2_2") (pintype "passive"))
      (node (ref "R42") (pin "2") (pinfunction "2_2") (pintype "passive"))
      (node (ref "R43") (pin "1") (pinfunction "1_1") (pintype "passive"))
      (node (ref "U5") (pin "10") (pinfunction "IN2-_10") (pintype "input"))
    )
    (net (code "74") (name "Net-(C36-P$1)") (class "Default")
      (node (ref "C36") (pin "1") (pinfunction "P$1_1") (pintype "passive"))
      (node (ref "R48") (pin "2") (pinfunction "2_2") (pintype "passive"))
      (node (ref "R50") (pin "2") (pinfunction "2_2") (pintype "passive"))
      (node (ref "U6") (pin "16") (pinfunction "IN1+_16") (pintype "input"))
    )
    (net (code "75") (name "Net-(C36-P$2)") (class "Default")
      (node (ref "C36") (pin "2") (pinfunction "P$2_2") (pintype "passive"))
      (node (ref "R49") (pin "2") (pinfunction "2_2") (pintype "passive"))
      (node (ref "R50") (pin "1") (pinfunction "1_1") (pintype "passive"))
      (node (ref "U6") (pin "15") (pinfunction "IN1-_15") (pintype "input"))
    )
    (net (code "76") (name "Net-(C37-P$1)") (class "Default")
      (node (ref "C37") (pin "1") (pinfunction "P$1_1") (pintype "passive"))
      (node (ref "R51") (pin "2") (pinfunction "2_2") (pintype "passive"))
      (node (ref "R53") (pin "2") (pinfunction "2_2") (pintype "passive"))
      (node (ref "U6") (pin "9") (pinfunction "IN2+_9") (pintype "input"))
    )
    (net (code "77") (name "Net-(C37-P$2)") (class "Default")
      (node (ref "C37") (pin "2") (pinfunction "P$2_2") (pintype "passive"))
      (node (ref "R52") (pin "2") (pinfunction "2_2") (pintype "passive"))
      (node (ref "R53") (pin "1") (pinfunction "1_1") (pintype "passive"))
      (node (ref "U6") (pin "10") (pinfunction "IN2-_10") (pintype "input"))
    )
    (net (code "78") (name "Net-(IC2-FB)") (class "Default")
      (node (ref "IC2") (pin "4") (pinfunction "FB_4") (pintype "input"))
      (node (ref "R1") (pin "2") (pinfunction "2_2") (pintype "passive"))
      (node (ref "R2") (pin "2") (pinfunction "2_2") (pintype "passive"))
    )
    (net (code "79") (name "Net-(IC2-OUT)") (class "Default")
      (node (ref "D8") (pin "C") (pinfunction "C_C") (pintype "passive"))
      (node (ref "IC2") (pin "2") (pinfunction "OUT_2") (pintype "output"))
      (node (ref "L1") (pin "1") (pinfunction "1_1") (pintype "passive"))
    )
    (net (code "80") (name "Net-(OK1-A)") (class "Default")
      (node (ref "OK1") (pin "1") (pinfunction "A_1") (pintype "passive"))
      (node (ref "R11") (pin "1") (pinfunction "1_1") (pintype "passive"))
    )
    (net (code "81") (name "Net-(OK1-BAS)") (class "Default")
      (node (ref "OK1") (pin "6") (pinfunction "BAS_6") (pintype "passive"))
      (node (ref "R9") (pin "1") (pinfunction "1_1") (pintype "passive"))
    )
    (net (code "82") (name "Net-(OK2-A)") (class "Default")
      (node (ref "OK2") (pin "1") (pinfunction "A_1") (pintype "passive"))
      (node (ref "R14") (pin "1") (pinfunction "1_1") (pintype "passive"))
    )
    (net (code "83") (name "Net-(OK2-BAS)") (class "Default")
      (node (ref "OK2") (pin "6") (pinfunction "BAS_6") (pintype "passive"))
      (node (ref "R10") (pin "1") (pinfunction "1_1") (pintype "passive"))
    )
    (net (code "84") (name "Net-(OK3-A)") (class "Default")
      (node (ref "OK3") (pin "1") (pinfunction "A_1") (pintype "passive"))
      (node (ref "R18") (pin "1") (pinfunction "1_1") (pintype "passive"))
    )
    (net (code "85") (name "Net-(OK3-BAS)") (class "Default")
      (node (ref "OK3") (pin "6") (pinfunction "BAS_6") (pintype "passive"))
      (node (ref "R16") (pin "1") (pinfunction "1_1") (pintype "passive"))
    )
    (net (code "86") (name "Net-(OK4-A)") (class "Default")
      (node (ref "OK4") (pin "1") (pinfunction "A_1") (pintype "passive"))
      (node (ref "R21") (pin "1") (pinfunction "1_1") (pintype "passive"))
    )
    (net (code "87") (name "Net-(OK4-BAS)") (class "Default")
      (node (ref "OK4") (pin "6") (pinfunction "BAS_6") (pintype "passive"))
      (node (ref "R20") (pin "1") (pinfunction "1_1") (pintype "passive"))
    )
    (net (code "88") (name "Net-(OK5-A)") (class "Default")
      (node (ref "OK5") (pin "1") (pinfunction "A_1") (pintype "passive"))
      (node (ref "R26") (pin "1") (pinfunction "1_1") (pintype "passive"))
    )
    (net (code "89") (name "Net-(OK5-BAS)") (class "Default")
      (node (ref "OK5") (pin "6") (pinfunction "BAS_6") (pintype "passive"))
      (node (ref "R23") (pin "1") (pinfunction "1_1") (pintype "passive"))
    )
    (net (code "90") (name "Net-(OK6-A)") (class "Default")
      (node (ref "OK6") (pin "1") (pinfunction "A_1") (pintype "passive"))
      (node (ref "R29") (pin "1") (pinfunction "1_1") (pintype "passive"))
    )
    (net (code "91") (name "Net-(OK6-BAS)") (class "Default")
      (node (ref "OK6") (pin "6") (pinfunction "BAS_6") (pintype "passive"))
      (node (ref "R28") (pin "1") (pinfunction "1_1") (pintype "passive"))
    )
    (net (code "92") (name "Net-(Q1-B)") (class "Default")
      (node (ref "Q1") (pin "1") (pinfunction "B_1") (pintype "passive"))
      (node (ref "R24") (pin "2") (pinfunction "2_2") (pintype "passive"))
    )
    (net (code "93") (name "Net-(Q2-B)") (class "Default")
      (node (ref "Q2") (pin "1") (pinfunction "B_1") (pintype "passive"))
      (node (ref "R25") (pin "2") (pinfunction "2_2") (pintype "passive"))
    )
    (net (code "94") (name "Net-(Q3-B)") (class "Default")
      (node (ref "Q3") (pin "1") (pinfunction "B_1") (pintype "passive"))
      (node (ref "R17") (pin "1") (pinfunction "1_1") (pintype "passive"))
    )
    (net (code "95") (name "Net-(Q11-B)") (class "Default")
      (node (ref "Q11") (pin "1") (pinfunction "B_1") (pintype "passive"))
      (node (ref "R32") (pin "2") (pinfunction "2_2") (pintype "passive"))
    )
    (net (code "96") (name "Net-(S1-S)") (class "Default")
      (node (ref "R54") (pin "2") (pinfunction "2_2") (pintype "passive"))
      (node (ref "S1") (pin "3") (pinfunction "S_3") (pintype "passive"))
    )
    (net (code "97") (name "Net-(S2-S)") (class "Default")
      (node (ref "R30") (pin "2") (pinfunction "2_2") (pintype "passive"))
      (node (ref "S2") (pin "3") (pinfunction "S_3") (pintype "passive"))
    )
    (net (code "98") (name "Net-(S3-S)") (class "Default")
      (node (ref "R56") (pin "2") (pinfunction "2_2") (pintype "passive"))
      (node (ref "S3") (pin "3") (pinfunction "S_3") (pintype "passive"))
    )
    (net (code "99") (name "Net-(S4-S)") (class "Default")
      (node (ref "R58") (pin "2") (pinfunction "2_2") (pintype "passive"))
      (node (ref "S4") (pin "3") (pinfunction "S_3") (pintype "passive"))
    )
    (net (code "100") (name "Net-(U$19-VIN+)") (class "Default")
      (node (ref "R6") (pin "1") (pinfunction "1_1") (pintype "passive"))
      (node (ref "R8") (pin "2") (pinfunction "2_2") (pintype "passive"))
      (node (ref "U$19") (pin "3") (pinfunction "VIN+_3") (pintype "input"))
    )
    (net (code "101") (name "Net-(U$24-VIN+)") (class "Default")
      (node (ref "R4") (pin "1") (pinfunction "1_1") (pintype "passive"))
      (node (ref "R5") (pin "2") (pinfunction "2_2") (pintype "passive"))
      (node (ref "U$24") (pin "3") (pinfunction "VIN+_3") (pintype "input"))
    )
    (net (code "102") (name "Net-(U5-COUT1)") (class "Default")
      (node (ref "R45") (pin "1") (pinfunction "1_1") (pintype "passive"))
      (node (ref "U5") (pin "4") (pinfunction "COUT1_4") (pintype "output"))
      (node (ref "U7") (pin "5") (pinfunction "2A_5") (pintype "input"))
    )
    (net (code "103") (name "Net-(U5-COUT2)") (class "Default")
      (node (ref "R44") (pin "1") (pinfunction "1_1") (pintype "passive"))
      (node (ref "U5") (pin "5") (pinfunction "COUT2_5") (pintype "output"))
      (node (ref "U7") (pin "3") (pinfunction "1A_3") (pintype "input"))
    )
    (net (code "104") (name "Net-(U6-COUT1)") (class "Default")
      (node (ref "R47") (pin "1") (pinfunction "1_1") (pintype "passive"))
      (node (ref "U6") (pin "4") (pinfunction "COUT1_4") (pintype "output"))
      (node (ref "U7") (pin "9") (pinfunction "4A_9") (pintype "input"))
    )
    (net (code "105") (name "Net-(U6-COUT2)") (class "Default")
      (node (ref "R46") (pin "1") (pinfunction "1_1") (pintype "passive"))
      (node (ref "U6") (pin "5") (pinfunction "COUT2_5") (pintype "output"))
      (node (ref "U7") (pin "7") (pinfunction "3A_7") (pintype "input"))
    )
    (net (code "106") (name "Net-(U8-CH0)") (class "Default")
      (node (ref "R54") (pin "1") (pinfunction "1_1") (pintype "passive"))
      (node (ref "R55") (pin "2") (pinfunction "2_2") (pintype "passive"))
      (node (ref "U8") (pin "1") (pinfunction "CH0_1") (pintype "input"))
    )
    (net (code "107") (name "Net-(U8-CH1)") (class "Default")
      (node (ref "R30") (pin "1") (pinfunction "1_1") (pintype "passive"))
      (node (ref "R31") (pin "2") (pinfunction "2_2") (pintype "passive"))
      (node (ref "U8") (pin "2") (pinfunction "CH1_2") (pintype "input"))
    )
    (net (code "108") (name "Net-(U8-CH2)") (class "Default")
      (node (ref "R56") (pin "1") (pinfunction "1_1") (pintype "passive"))
      (node (ref "R57") (pin "2") (pinfunction "2_2") (pintype "passive"))
      (node (ref "U8") (pin "3") (pinfunction "CH2_3") (pintype "input"))
    )
    (net (code "109") (name "Net-(U8-CH3)") (class "Default")
      (node (ref "R58") (pin "1") (pinfunction "1_1") (pintype "passive"))
      (node (ref "R59") (pin "2") (pinfunction "2_2") (pintype "passive"))
      (node (ref "U8") (pin "4") (pinfunction "CH3_4") (pintype "input"))
    )
    (net (code "110") (name "OC1") (class "Default")
      (node (ref "R11") (pin "2") (pinfunction "2_2") (pintype "passive"))
      (node (ref "U$1") (pin "P$36") (pinfunction "PC7_P$36") (pintype "bidirectional"))
    )
    (net (code "111") (name "OC2") (class "Default")
      (node (ref "R14") (pin "2") (pinfunction "2_2") (pintype "passive"))
      (node (ref "U$1") (pin "P$35") (pinfunction "PC6_P$35") (pintype "bidirectional"))
    )
    (net (code "112") (name "OC3") (class "Default")
      (node (ref "R18") (pin "2") (pinfunction "2_2") (pintype "passive"))
      (node (ref "U$1") (pin "P$38") (pinfunction "PC9_P$38") (pintype "bidirectional"))
    )
    (net (code "113") (name "OC4") (class "Default")
      (node (ref "R21") (pin "2") (pinfunction "2_2") (pintype "passive"))
      (node (ref "U$1") (pin "P$37") (pinfunction "PC8_P$37") (pintype "bidirectional"))
    )
    (net (code "114") (name "OC5") (class "Default")
      (node (ref "R26") (pin "2") (pinfunction "2_2") (pintype "passive"))
      (node (ref "U$1") (pin "P$40") (pinfunction "PA9_P$40") (pintype "bidirectional"))
    )
    (net (code "115") (name "OC6") (class "Default")
      (node (ref "R29") (pin "2") (pinfunction "2_2") (pintype "passive"))
      (node (ref "U$1") (pin "P$39") (pinfunction "PA8_P$39") (pintype "bidirectional"))
    )
    (net (code "116") (name "OILP") (class "Default")
      (node (ref "J1") (pin "C1") (pinfunction "C_C1") (pintype "bidirectional"))
      (node (ref "S1") (pin "2") (pinfunction "P_2") (pintype "passive"))
    )
    (net (code "117") (name "OILPI") (class "Default")
      (node (ref "R38") (pin "2") (pinfunction "2_2") (pintype "passive"))
      (node (ref "S1") (pin "1") (pinfunction "O_1") (pintype "passive"))
      (node (ref "U$1") (pin "P$16") (pinfunction "PE13_P$16") (pintype "bidirectional"))
    )
    (net (code "118") (name "RLY1") (class "Default")
      (node (ref "D1") (pin "C") (pinfunction "C_C") (pintype "passive"))
      (node (ref "J1") (pin "L1") (pinfunction "L_L1") (pintype "bidirectional"))
      (node (ref "OK1") (pin "5") (pinfunction "COL_5") (pintype "passive"))
    )
    (net (code "119") (name "RLY2") (class "Default")
      (node (ref "D3") (pin "C") (pinfunction "C_C") (pintype "passive"))
      (node (ref "J1") (pin "M1") (pinfunction "M_M1") (pintype "bidirectional"))
      (node (ref "OK2") (pin "5") (pinfunction "COL_5") (pintype "passive"))
    )
    (net (code "120") (name "RLY3") (class "Default")
      (node (ref "D4") (pin "C") (pinfunction "C_C") (pintype "passive"))
      (node (ref "J1") (pin "L2") (pinfunction "L_L2") (pintype "bidirectional"))
      (node (ref "OK3") (pin "5") (pinfunction "COL_5") (pintype "passive"))
    )
    (net (code "121") (name "RLY4") (class "Default")
      (node (ref "D5") (pin "C") (pinfunction "C_C") (pintype "passive"))
      (node (ref "J1") (pin "M2") (pinfunction "M_M2") (pintype "bidirectional"))
      (node (ref "OK4") (pin "5") (pinfunction "COL_5") (pintype "passive"))
    )
    (net (code "122") (name "RLY5") (class "Default")
      (node (ref "D6") (pin "C") (pinfunction "C_C") (pintype "passive"))
      (node (ref "J1") (pin "L3") (pinfunction "L_L3") (pintype "bidirectional"))
      (node (ref "OK5") (pin "5") (pinfunction "COL_5") (pintype "passive"))
    )
    (net (code "123") (name "RLY6") (class "Default")
      (node (ref "D7") (pin "C") (pinfunction "C_C") (pintype "passive"))
      (node (ref "J1") (pin "M3") (pinfunction "M_M3") (pintype "bidirectional"))
      (node (ref "OK6") (pin "5") (pinfunction "COL_5") (pintype "passive"))
    )
    (net (code "124") (name "RPM1") (class "Default")
      (node (ref "U$1") (pin "P$50") (pinfunction "PD4_P$50") (pintype "bidirectional"))
      (node (ref "U7") (pin "10") (pinfunction "4Y_10") (pintype "output"))
    )
    (net (code "125") (name "RPM1GIN") (class "Default")
      (node (ref "J2") (pin "B4") (pinfunction "B_B4") (pintype "bidirectional"))
      (node (ref "R42") (pin "1") (pinfunction "1_1") (pintype "passive"))
    )
    (net (code "126") (name "RPM1IN") (class "Default")
      (node (ref "J2") (pin "A4") (pinfunction "A_A4") (pintype "bidirectional"))
      (node (ref "R41") (pin "1") (pinfunction "1_1") (pintype "passive"))
    )
    (net (code "127") (name "RPM2") (class "Default")
      (node (ref "U$1") (pin "P$49") (pinfunction "PD3_P$49") (pintype "bidirectional"))
      (node (ref "U7") (pin "6") (pinfunction "3Y_6") (pintype "output"))
    )
    (net (code "128") (name "RPM2GIN") (class "Default")
      (node (ref "J2") (pin "B3") (pinfunction "B_B3") (pintype "bidirectional"))
      (node (ref "R27") (pin "1") (pinfunction "1_1") (pintype "passive"))
    )
    (net (code "129") (name "RPM2IN") (class "Default")
      (node (ref "J2") (pin "A3") (pinfunction "A_A3") (pintype "bidirectional"))
      (node (ref "R39") (pin "1") (pinfunction "1_1") (pintype "passive"))
    )
    (net (code "130") (name "RPM3") (class "Default")
      (node (ref "U$1") (pin "P$48") (pinfunction "PD2_P$48") (pintype "bidirectional"))
      (node (ref "U7") (pin "4") (pinfunction "2Y_4") (pintype "output"))
    )
    (net (code "131") (name "RPM3GIN") (class "Default")
      (node (ref "J2") (pin "B2") (pinfunction "B_B2") (pintype "bidirectional"))
      (node (ref "R52") (pin "1") (pinfunction "1_1") (pintype "passive"))
    )
    (net (code "132") (name "RPM3IN") (class "Default")
      (node (ref "J2") (pin "A2") (pinfunction "A_A2") (pintype "bidirectional"))
      (node (ref "R51") (pin "1") (pinfunction "1_1") (pintype "passive"))
    )
    (net (code "133") (name "RPM4") (class "Default")
      (node (ref "U$1") (pin "P$53") (pinfunction "PD7_P$53") (pintype "bidirectional"))
      (node (ref "U7") (pin "2") (pinfunction "1Y_2") (pintype "output"))
    )
    (net (code "134") (name "RPM4GIN") (class "Default")
      (node (ref "J2") (pin "B1") (pinfunction "B_B1") (pintype "bidirectional"))
      (node (ref "R48") (pin "1") (pinfunction "1_1") (pintype "passive"))
    )
    (net (code "135") (name "RPM4IN") (class "Default")
      (node (ref "J2") (pin "A1") (pinfunction "A_A1") (pintype "bidirectional"))
      (node (ref "R49") (pin "1") (pinfunction "1_1") (pintype "passive"))
    )
    (net (code "136") (name "RS232RX") (class "Default")
      (node (ref "J2") (pin "C1") (pinfunction "C_C1") (pintype "bidirectional"))
      (node (ref "U2") (pin "8") (pinfunction "R2IN_8") (pintype "input"))
    )
    (net (code "137") (name "RS232TX") (class "Default")
      (node (ref "J2") (pin "C2") (pinfunction "C_C2") (pintype "bidirectional"))
      (node (ref "U2") (pin "7") (pinfunction "T2OUT_7") (pintype "output"))
    )
    (net (code "138") (name "SCK") (class "Default")
      (node (ref "JP1") (pin "3") (pinfunction "3_3") (pintype "passive"))
      (node (ref "U$1") (pin "P$24") (pinfunction "PB13_P$24") (pintype "bidirectional"))
      (node (ref "U8") (pin "11") (pinfunction "CLK_11") (pintype "input"))
      (node (ref "U9") (pin "16") (pinfunction "SCLK_16") (pintype "input"))
    )
    (net (code "139") (name "SPEED") (class "Default")
      (node (ref "J2") (pin "J3") (pinfunction "J_J3") (pintype "bidirectional"))
      (node (ref "U$33") (pin "3") (pinfunction "VIN+_3") (pintype "input"))
    )
    (net (code "140") (name "SPEEDB") (class "Default")
      (node (ref "U$1") (pin "P$77") (pinfunction "PA2_P$77") (pintype "bidirectional"))
      (node (ref "U$33") (pin "1") (pinfunction "VOUT_1") (pintype "output"))
      (node (ref "U$33") (pin "4") (pinfunction "VIN-_4") (pintype "input"))
    )
    (net (code "141") (name "TRAVEL1") (class "Default")
      (node (ref "J2") (pin "L3") (pinfunction "L_L3") (pintype "bidirectional"))
      (node (ref "U$30") (pin "3") (pinfunction "VIN+_3") (pintype "input"))
    )
    (net (code "142") (name "TRAVEL1B") (class "Default")
      (node (ref "U$1") (pin "P$1") (pinfunction "PA3_P$1") (pintype "bidirectional"))
      (node (ref "U$30") (pin "1") (pinfunction "VOUT_1") (pintype "output"))
      (node (ref "U$30") (pin "4") (pinfunction "VIN-_4") (pintype "input"))
    )
    (net (code "143") (name "TRAVEL2") (class "Default")
      (node (ref "J2") (pin "L4") (pinfunction "L_L4") (pintype "bidirectional"))
      (node (ref "U$34") (pin "3") (pinfunction "VIN+_3") (pintype "input"))
    )
    (net (code "144") (name "TRAVEL2B") (class "Default")
      (node (ref "U$1") (pin "P$2") (pinfunction "PA4_P$2") (pintype "bidirectional"))
      (node (ref "U$34") (pin "1") (pinfunction "VOUT_1") (pintype "output"))
      (node (ref "U$34") (pin "4") (pinfunction "VIN-_4") (pintype "input"))
    )
    (net (code "145") (name "TRAVEL3") (class "Default")
      (node (ref "J2") (pin "L2") (pinfunction "L_L2") (pintype "bidirectional"))
      (node (ref "U$37") (pin "3") (pinfunction "VIN+_3") (pintype "input"))
    )
    (net (code "146") (name "TRAVEL3B") (class "Default")
      (node (ref "U$1") (pin "P$3") (pinfunction "PA5_P$3") (pintype "bidirectional"))
      (node (ref "U$37") (pin "1") (pinfunction "VOUT_1") (pintype "output"))
      (node (ref "U$37") (pin "4") (pinfunction "VIN-_4") (pintype "input"))
    )
    (net (code "147") (name "TRAVEL4") (class "Default")
      (node (ref "J2") (pin "L1") (pinfunction "L_L1") (pintype "bidirectional"))
      (node (ref "U$40") (pin "3") (pinfunction "VIN+_3") (pintype "input"))
    )
    (net (code "148") (name "TRAVEL4B") (class "Default")
      (node (ref "U$1") (pin "P$4") (pinfunction "PA6_P$4") (pintype "bidirectional"))
      (node (ref "U$40") (pin "1") (pinfunction "VOUT_1") (pintype "output"))
      (node (ref "U$40") (pin "4") (pinfunction "VIN-_4") (pintype "input"))
    )
    (net (code "149") (name "VCC") (class "Default")
      (node (ref "J1") (pin "L4") (pinfunction "L_L4") (pintype "bidirectional"))
      (node (ref "PTC2") (pin "P$2") (pinfunction "2_P$2") (pintype "passive"))
    )
    (net (code "150") (name "VOUT") (class "Default")
      (node (ref "J1") (pin "H3") (pinfunction "H_H3") (pintype "bidirectional"))
      (node (ref "U9") (pin "6") (pinfunction "VOUTA_6") (pintype "output"))
    )
    (net (code "151") (name "VTEMP") (class "Default")
      (node (ref "J2") (pin "F1") (pinfunction "F_F1") (pintype "bidirectional"))
      (node (ref "R13") (pin "2") (pinfunction "2_2") (pintype "passive"))
      (node (ref "U$45") (pin "3") (pinfunction "VIN+_3") (pintype "input"))
    )
    (net (code "152") (name "VTEMP2") (class "Default")
      (node (ref "J2") (pin "F3") (pinfunction "F_F3") (pintype "bidirectional"))
      (node (ref "R12") (pin "2") (pinfunction "2_2") (pintype "passive"))
      (node (ref "U$47") (pin "3") (pinfunction "VIN+_3") (pintype "input"))
    )
    (net (code "153") (name "VTEMP2B") (class "Default")
      (node (ref "U$1") (pin "P$74") (pinfunction "PC3_P$74") (pintype "bidirectional"))
      (node (ref "U$47") (pin "1") (pinfunction "VOUT_1") (pintype "output"))
      (node (ref "U$47") (pin "4") (pinfunction "VIN-_4") (pintype "input"))
    )
    (net (code "154") (name "VTEMPB") (class "Default")
      (node (ref "U$1") (pin "P$73") (pinfunction "PC2_P$73") (pintype "bidirectional"))
      (node (ref "U$45") (pin "1") (pinfunction "VOUT_1") (pintype "output"))
      (node (ref "U$45") (pin "4") (pinfunction "VIN-_4") (pintype "input"))
    )
    (net (code "155") (name "YAW") (class "Default")
      (node (ref "J1") (pin "A3") (pinfunction "A_A3") (pintype "bidirectional"))
      (node (ref "R6") (pin "2") (pinfunction "2_2") (pintype "passive"))
    )
    (net (code "156") (name "YAWO") (class "Default")
      (node (ref "R34") (pin "1") (pinfunction "1_1") (pintype "passive"))
      (node (ref "U$1") (pin "P$6") (pinfunction "PC4_P$6") (pintype "bidirectional"))
      (node (ref "U$19") (pin "1") (pinfunction "VOUT_1") (pintype "output"))
      (node (ref "U$19") (pin "4") (pinfunction "VIN-_4") (pintype "input"))
    )
    (net (code "157") (name "unconnected-(J1A-D-PadD1)") (class "Default")
      (node (ref "J1") (pin "D1") (pinfunction "D_D1") (pintype "bidirectional"))
    )
    (net (code "158") (name "unconnected-(J1B-H-PadH2)") (class "Default")
      (node (ref "J1") (pin "H2") (pinfunction "H_H2") (pintype "bidirectional"))
    )
    (net (code "159") (name "unconnected-(J1B-K-PadK2)") (class "Default")
      (node (ref "J1") (pin "K2") (pinfunction "K_K2") (pintype "bidirectional"))
    )
    (net (code "160") (name "unconnected-(U$1B-PD8-PadP$27)") (class "Default")
      (node (ref "U$1") (pin "P$27") (pinfunction "PD8_P$27") (pintype "bidirectional"))
    )
    (net (code "161") (name "unconnected-(U$1C-PB4-PadP$54)") (class "Default")
      (node (ref "U$1") (pin "P$54") (pinfunction "PB4_P$54") (pintype "bidirectional"))
    )
    (net (code "162") (name "unconnected-(U$1C-PB7-PadP$57)") (class "Default")
      (node (ref "U$1") (pin "P$57") (pinfunction "PB7_P$57") (pintype "bidirectional"))
    )
    (net (code "163") (name "unconnected-(U$1C-PB8-PadP$58)") (class "Default")
      (node (ref "U$1") (pin "P$58") (pinfunction "PB8_P$58") (pintype "bidirectional"))
    )
    (net (code "164") (name "unconnected-(U$1C-PB9-PadP$59)") (class "Default")
      (node (ref "U$1") (pin "P$59") (pinfunction "PB9_P$59") (pintype "bidirectional"))
    )
    (net (code "165") (name "unconnected-(U$1C-PC10-PadP$45)") (class "Default")
      (node (ref "U$1") (pin "P$45") (pinfunction "PC10_P$45") (pintype "bidirectional"))
    )
    (net (code "166") (name "unconnected-(U$1C-PC11-PadP$46)") (class "Default")
      (node (ref "U$1") (pin "P$46") (pinfunction "PC11_P$46") (pintype "bidirectional"))
    )
    (net (code "167") (name "unconnected-(U$1C-PC12-PadP$47)") (class "Default")
      (node (ref "U$1") (pin "P$47") (pinfunction "PC12_P$47") (pintype "bidirectional"))
    )
    (net (code "168") (name "unconnected-(U$1C-PE0-PadP$60)") (class "Default")
      (node (ref "U$1") (pin "P$60") (pinfunction "PE0_P$60") (pintype "bidirectional"))
    )
    (net (code "169") (name "unconnected-(U$1C-PE1-PadP$61)") (class "Default")
      (node (ref "U$1") (pin "P$61") (pinfunction "PE1_P$61") (pintype "bidirectional"))
    )
    (net (code "170") (name "unconnected-(U$1D-PC1-PadP$72)") (class "Default")
      (node (ref "U$1") (pin "P$72") (pinfunction "PC1_P$72") (pintype "bidirectional"))
    )
    (net (code "171") (name "unconnected-(U$1D-PE2-PadP$63)") (class "Default")
      (node (ref "U$1") (pin "P$63") (pinfunction "PE2_P$63") (pintype "bidirectional"))
    )
    (net (code "172") (name "unconnected-(U$1D-PE3-PadP$64)") (class "Default")
      (node (ref "U$1") (pin "P$64") (pinfunction "PE3_P$64") (pintype "bidirectional"))
    )
    (net (code "173") (name "unconnected-(U2-R1IN-Pad13)") (class "Default")
      (node (ref "U2") (pin "13") (pinfunction "R1IN_13") (pintype "input"))
    )
    (net (code "174") (name "unconnected-(U2-R1OUT-Pad12)") (class "Default")
      (node (ref "U2") (pin "12") (pinfunction "R1OUT_12") (pintype "output"))
    )
    (net (code "175") (name "unconnected-(U2-T1IN-Pad11)") (class "Default")
      (node (ref "U2") (pin "11") (pinfunction "T1IN_11") (pintype "input"))
    )
    (net (code "176") (name "unconnected-(U2-T1OUT-Pad14)") (class "Default")
      (node (ref "U2") (pin "14") (pinfunction "T1OUT_14") (pintype "output"))
    )
    (net (code "177") (name "unconnected-(U4-A7-Pad8)") (class "Default")
      (node (ref "U4") (pin "8") (pinfunction "A7_8") (pintype "bidirectional"))
    )
    (net (code "178") (name "unconnected-(U4-A8-Pad9)") (class "Default")
      (node (ref "U4") (pin "9") (pinfunction "A8_9") (pintype "bidirectional"))
    )
    (net (code "179") (name "unconnected-(U4-B7-Pad13)") (class "Default")
      (node (ref "U4") (pin "13") (pinfunction "B7_13") (pintype "bidirectional"))
    )
    (net (code "180") (name "unconnected-(U4-B8-Pad12)") (class "Default")
      (node (ref "U4") (pin "12") (pinfunction "B8_12") (pintype "bidirectional"))
    )
    (net (code "181") (name "unconnected-(U5-EXT1-Pad2)") (class "Default")
      (node (ref "U5") (pin "2") (pinfunction "EXT1_2") (pintype "input"))
    )
    (net (code "182") (name "unconnected-(U5-EXT2-Pad7)") (class "Default")
      (node (ref "U5") (pin "7") (pinfunction "EXT2_7") (pintype "input"))
    )
    (net (code "183") (name "unconnected-(U5-OUT2-Pad12)") (class "Default")
      (node (ref "U5") (pin "12") (pinfunction "OUT2_12") (pintype "output"))
    )
    (net (code "184") (name "unconnected-(U6-EXT1-Pad2)") (class "Default")
      (node (ref "U6") (pin "2") (pinfunction "EXT1_2") (pintype "input"))
    )
    (net (code "185") (name "unconnected-(U6-EXT2-Pad7)") (class "Default")
      (node (ref "U6") (pin "7") (pinfunction "EXT2_7") (pintype "input"))
    )
    (net (code "186") (name "unconnected-(U6-OUT2-Pad12)") (class "Default")
      (node (ref "U6") (pin "12") (pinfunction "OUT2_12") (pintype "output"))
    )
    (net (code "187") (name "unconnected-(U7-5A-Pad11)") (class "Default")
      (node (ref "U7") (pin "11") (pinfunction "5A_11") (pintype "input"))
    )
    (net (code "188") (name "unconnected-(U7-5Y-Pad12)") (class "Default")
      (node (ref "U7") (pin "12") (pinfunction "5Y_12") (pintype "output"))
    )
    (net (code "189") (name "unconnected-(U7-6A-Pad14)") (class "Default")
      (node (ref "U7") (pin "14") (pinfunction "6A_14") (pintype "input"))
    )
    (net (code "190") (name "unconnected-(U7-6Y-Pad15)") (class "Default")
      (node (ref "U7") (pin "15") (pinfunction "6Y_15") (pintype "output"))
    )
    (net (code "191") (name "unconnected-(U7-N.C.-Pad13)") (class "Default")
      (node (ref "U7") (pin "13") (pinfunction "N.C._13") (pintype "no_connect"))
    )
    (net (code "192") (name "unconnected-(U7-N.C._2-Pad16)") (class "Default")
      (node (ref "U7") (pin "16") (pinfunction "N.C._2_16") (pintype "no_connect"))
    )
    (net (code "193") (name "unconnected-(U8-NC-Pad6)") (class "Default")
      (node (ref "U8") (pin "6") (pinfunction "NC_6") (pintype "no_connect"))
    )
    (net (code "194") (name "unconnected-(U8-NC_2-Pad5)") (class "Default")
      (node (ref "U8") (pin "5") (pinfunction "NC_2_5") (pintype "no_connect"))
    )
    (net (code "195") (name "unconnected-(U9-VOUTB-Pad13)") (class "Default")
      (node (ref "U9") (pin "13") (pinfunction "VOUTB_13") (pintype "output"))
    )
    (net (code "196") (name "unconnected-(U9-VOUTC-Pad7)") (class "Default")
      (node (ref "U9") (pin "7") (pinfunction "VOUTC_7") (pintype "output"))
    )
    (net (code "197") (name "unconnected-(U9-VOUTD-Pad12)") (class "Default")
      (node (ref "U9") (pin "12") (pinfunction "VOUTD_12") (pintype "output"))
    )
  )
)
